# qo-100-lnb-controller.net
KiCad netlist of a schematic drawn in EAGLE
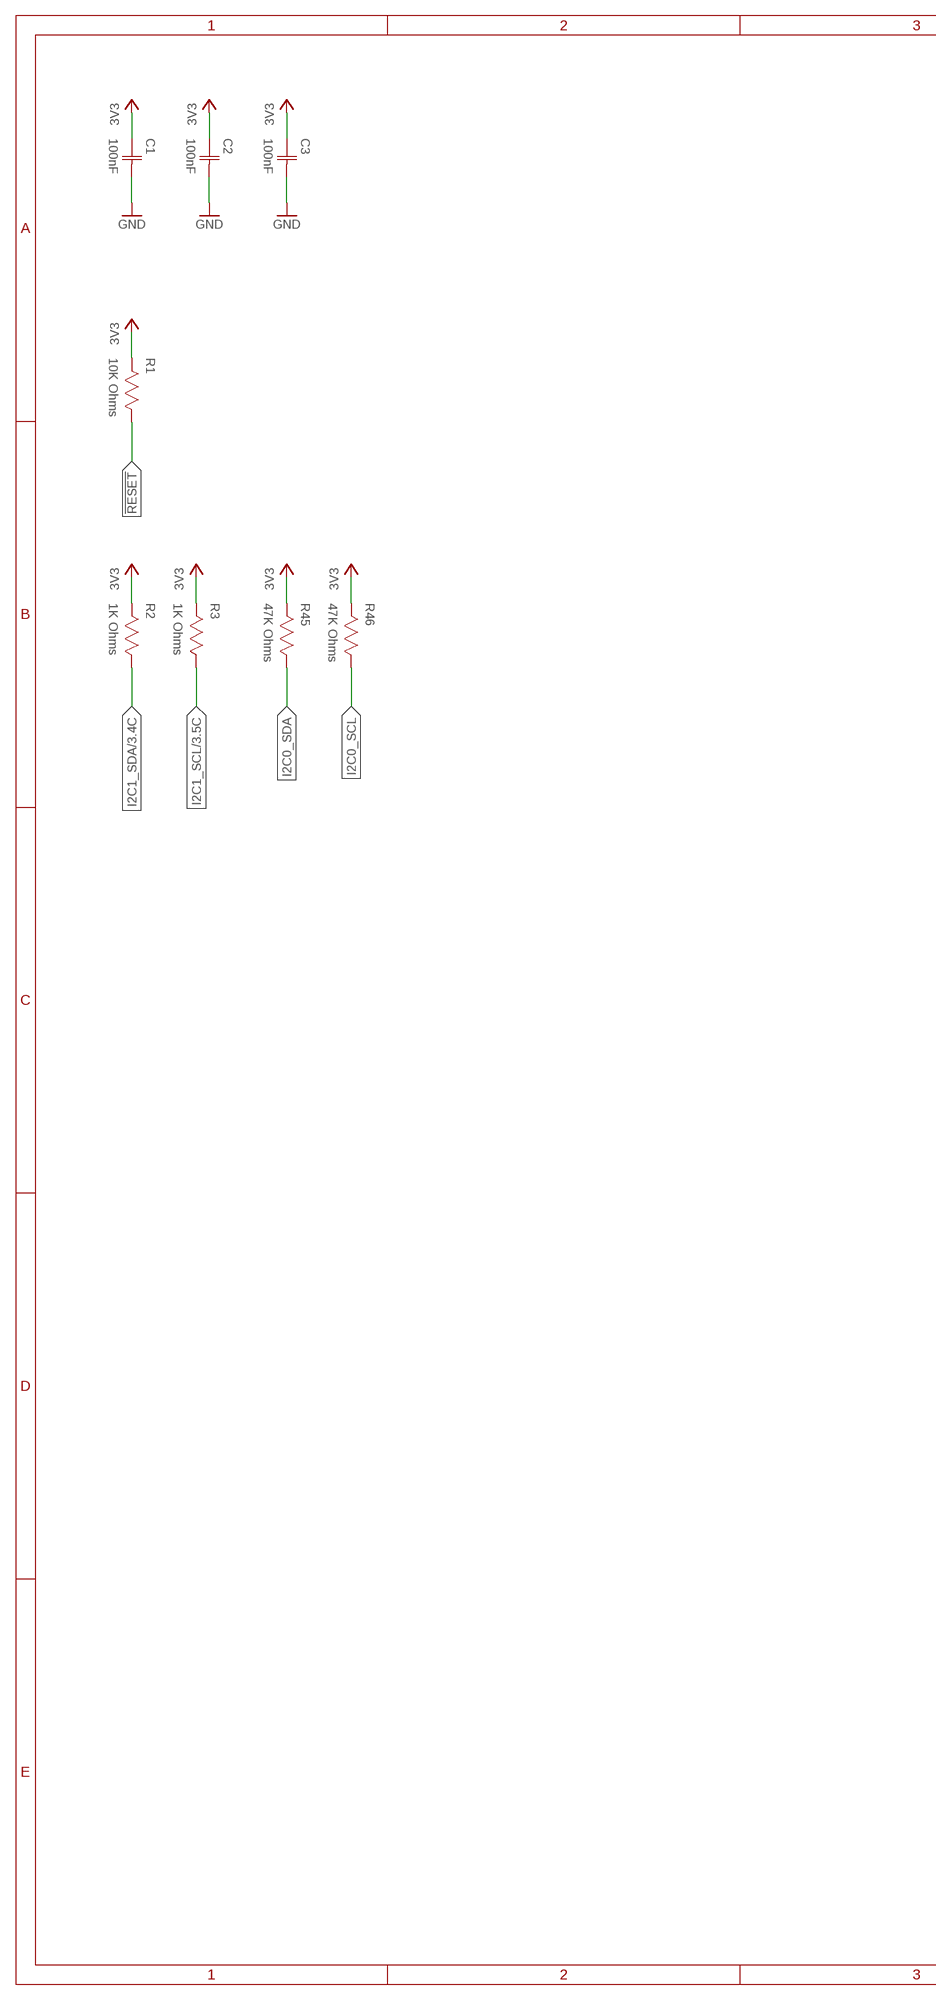
[diagram p0: schematic, sheet 1, part 1 of 2]
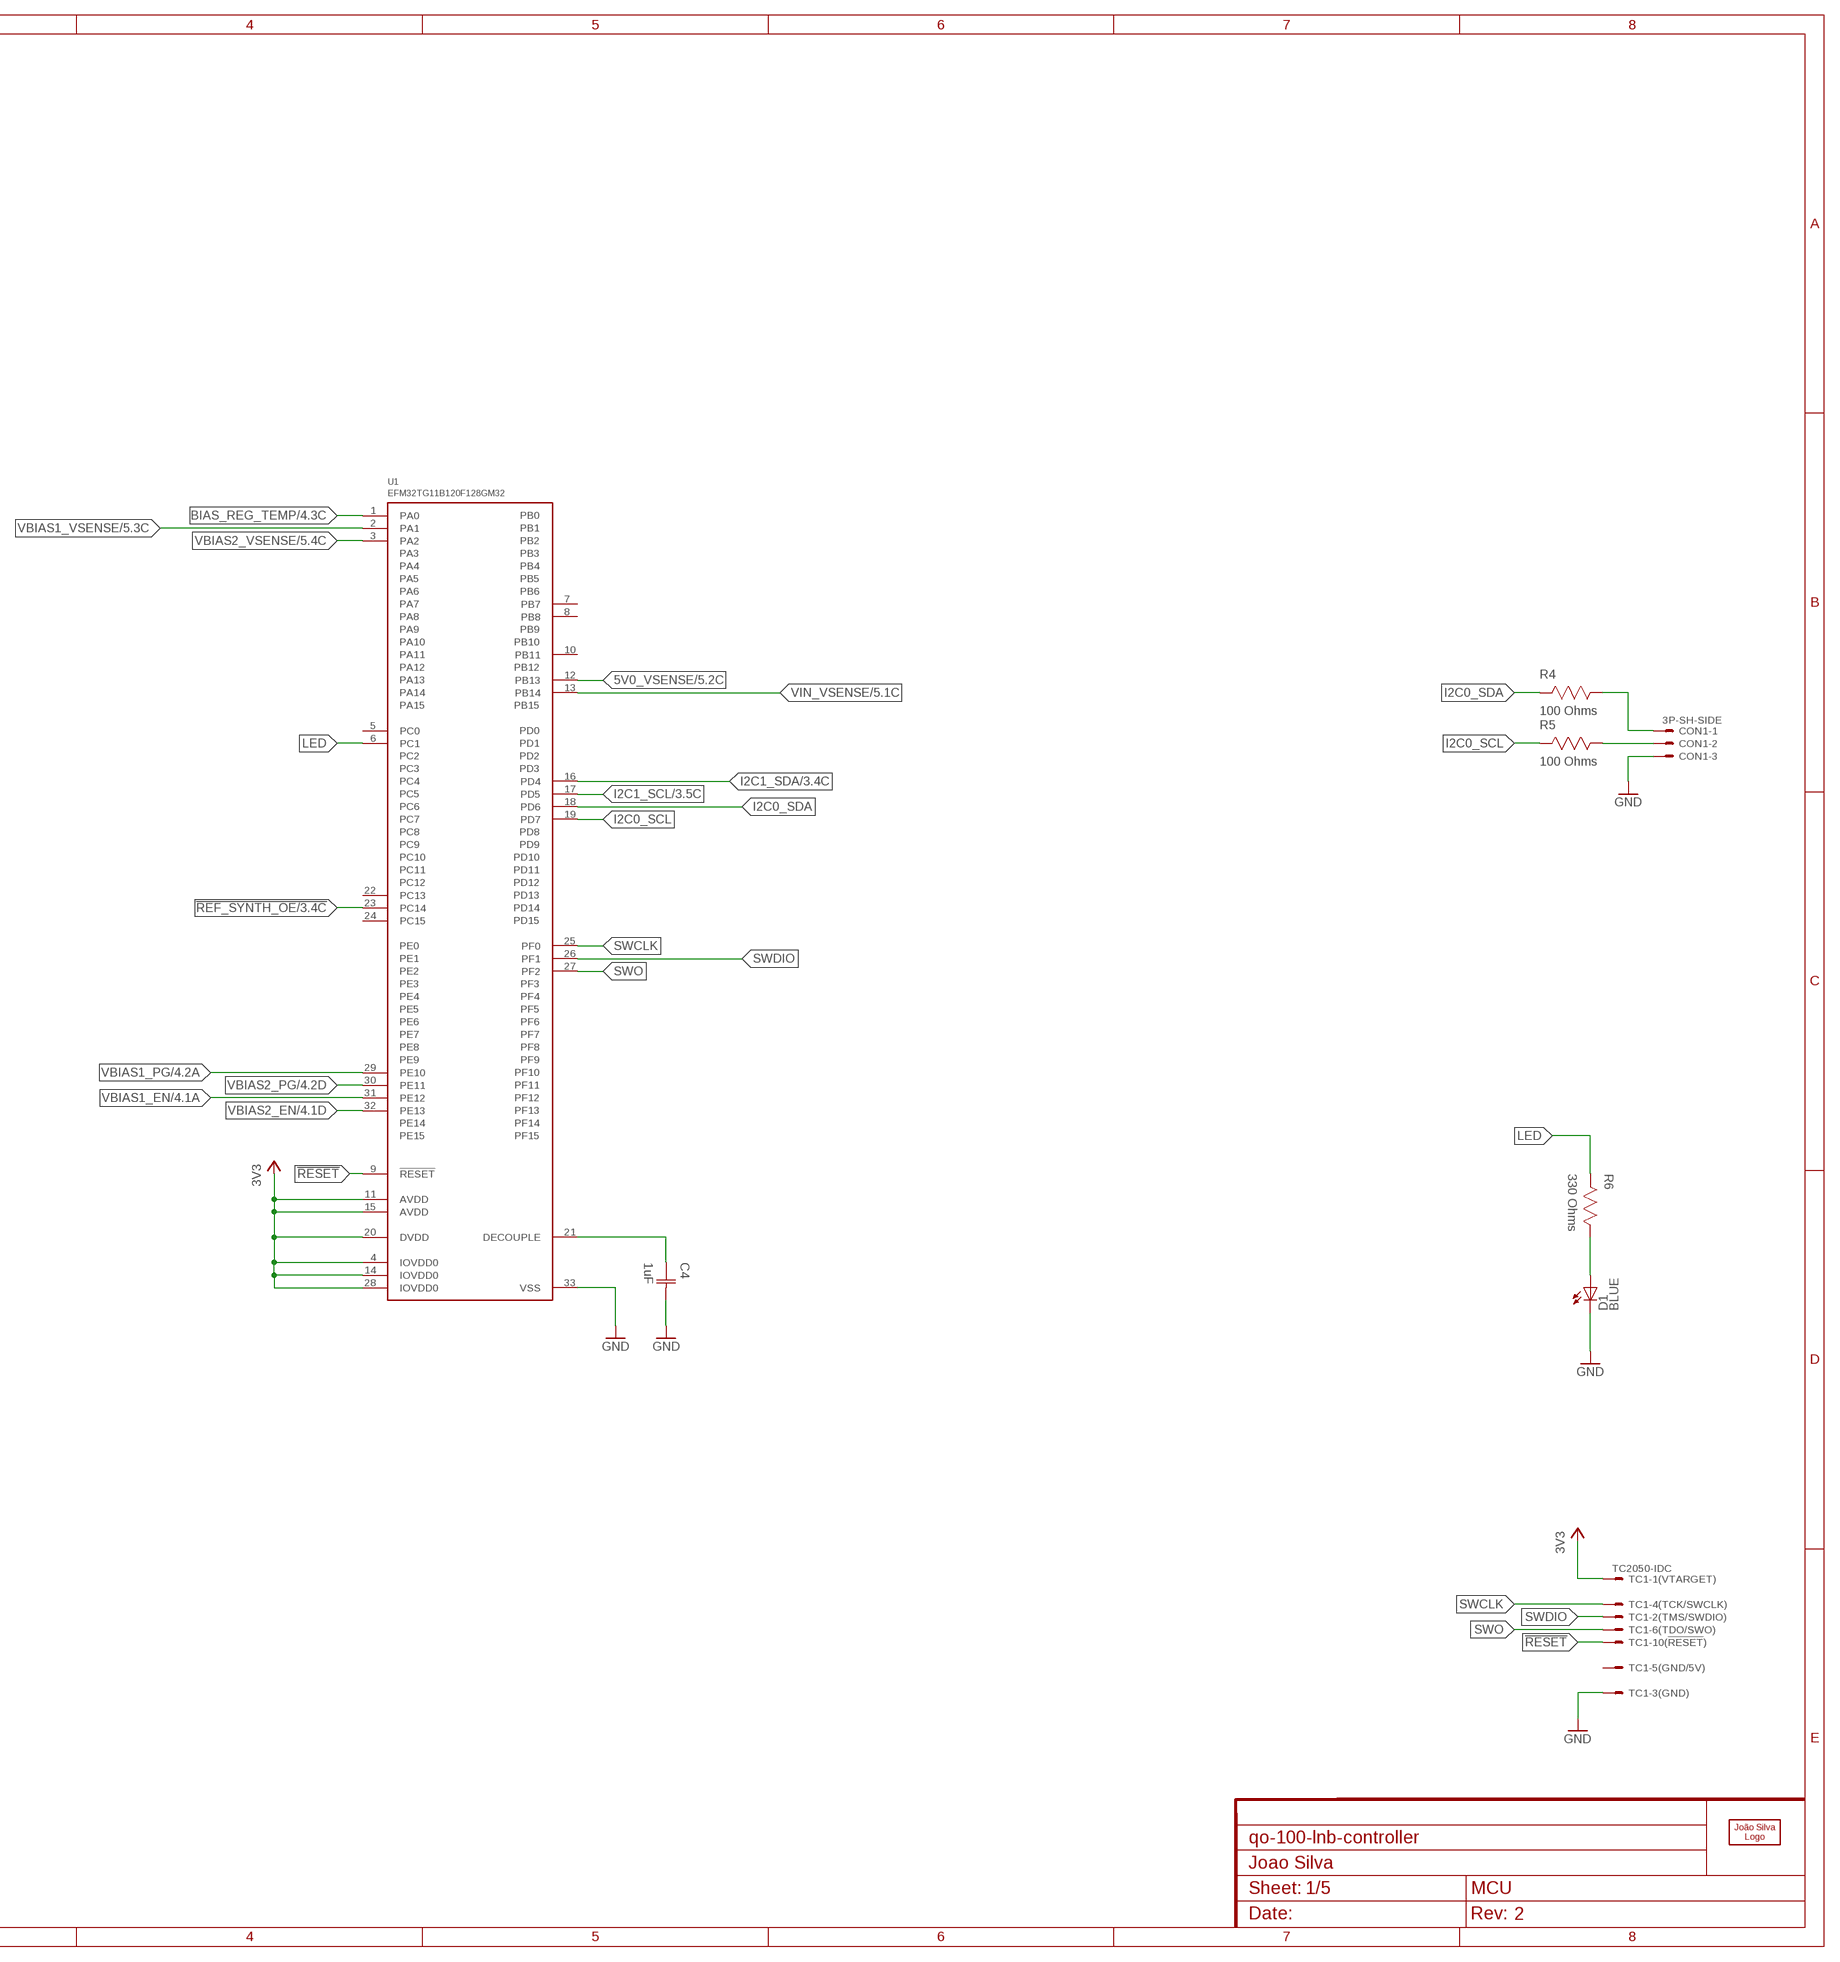
[diagram p1: schematic, sheet 1, part 2 of 2]
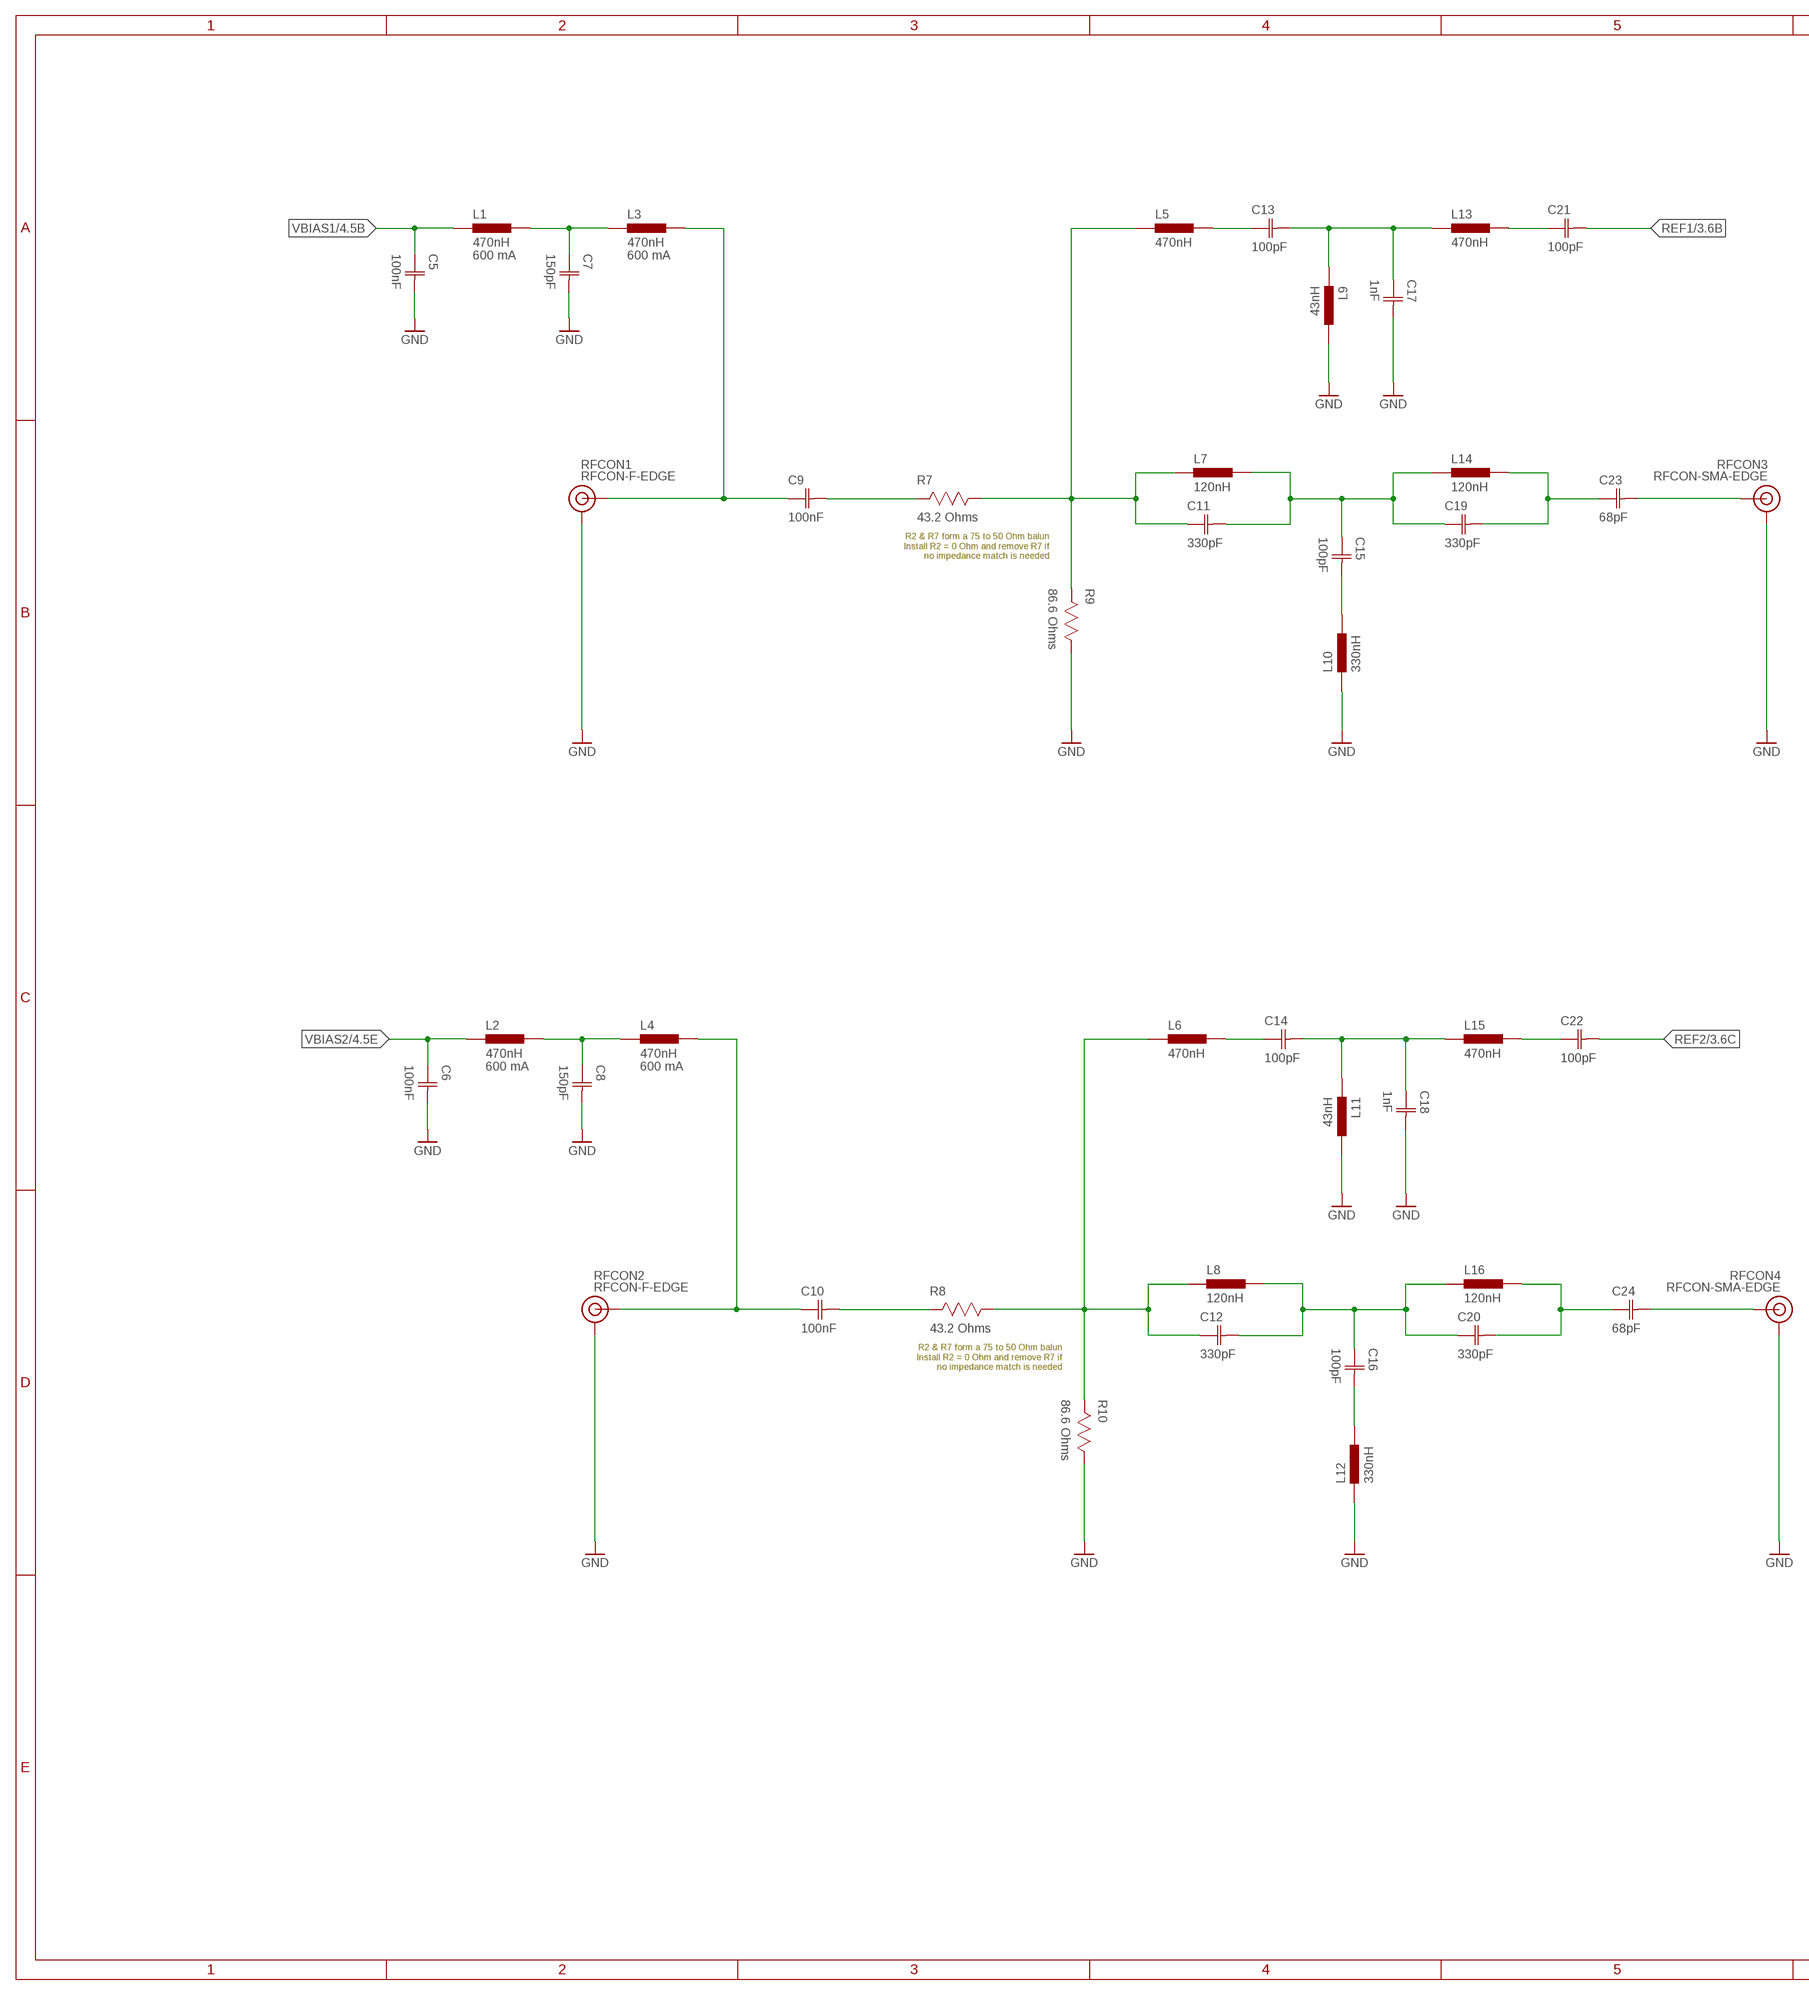
[diagram p2: schematic, sheet 2, part 1 of 2]
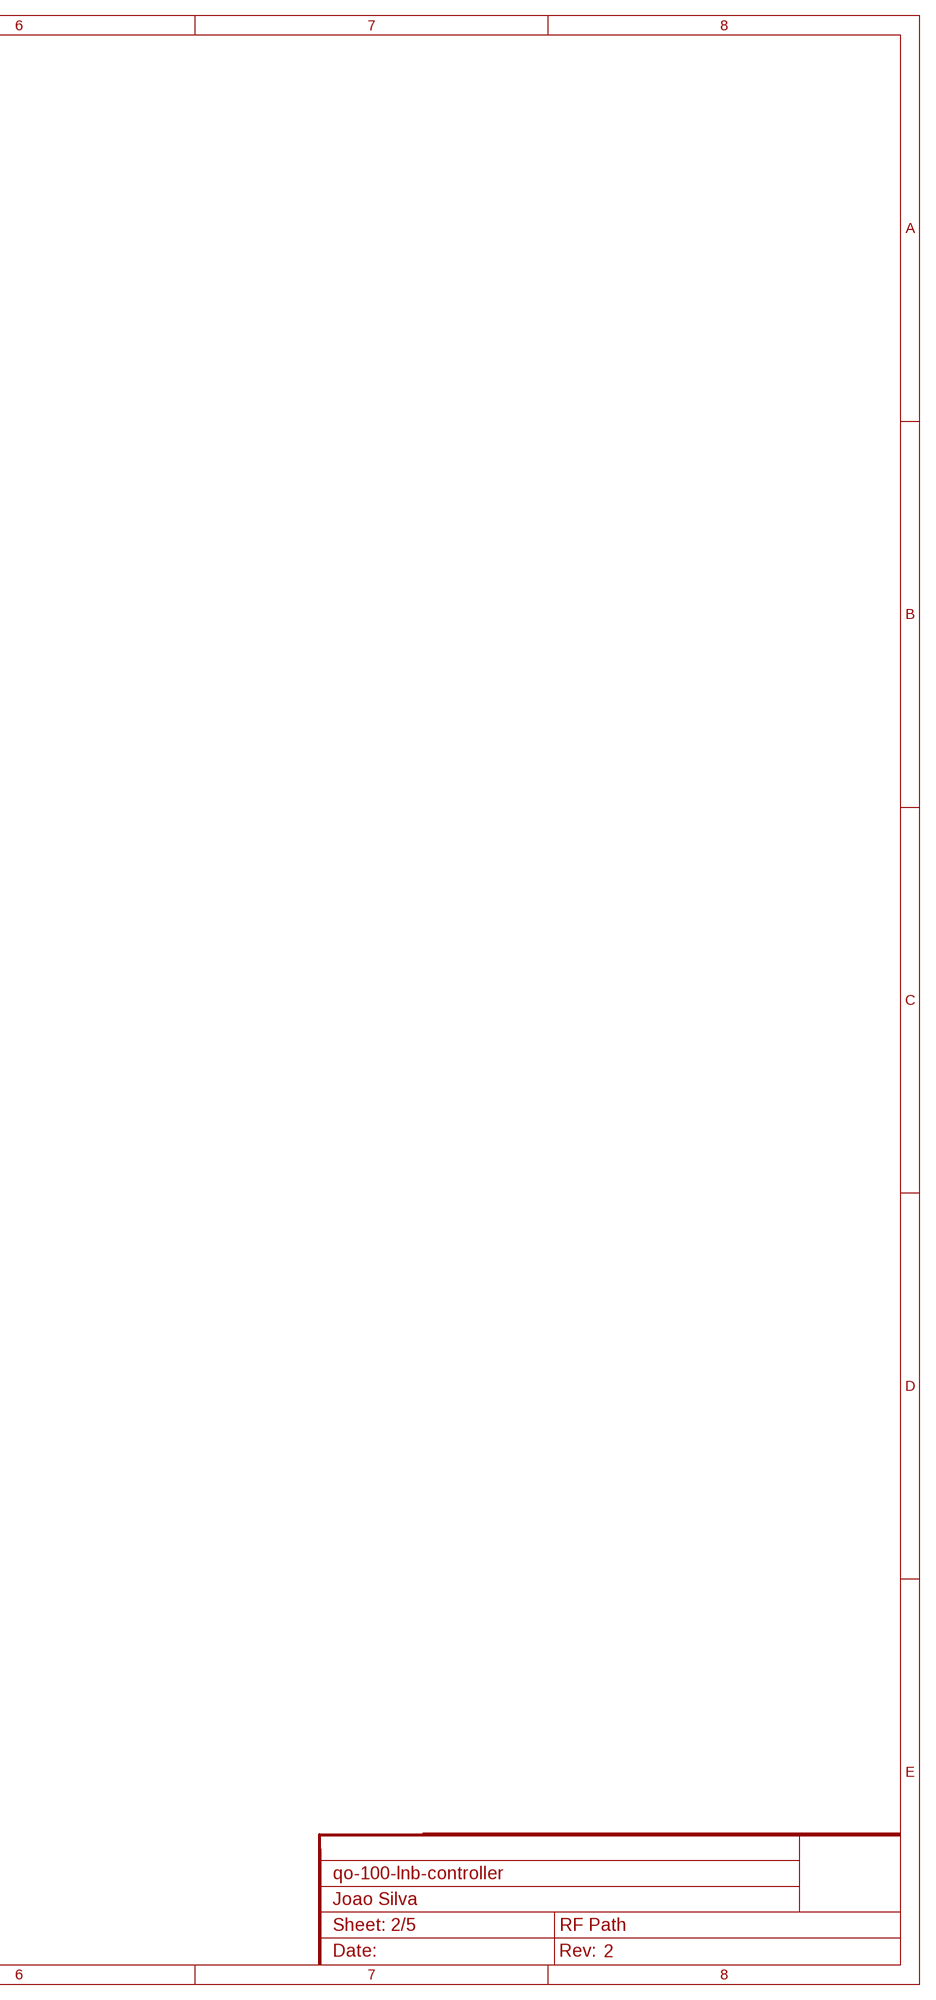
[diagram p3: schematic, sheet 2, part 2 of 2]
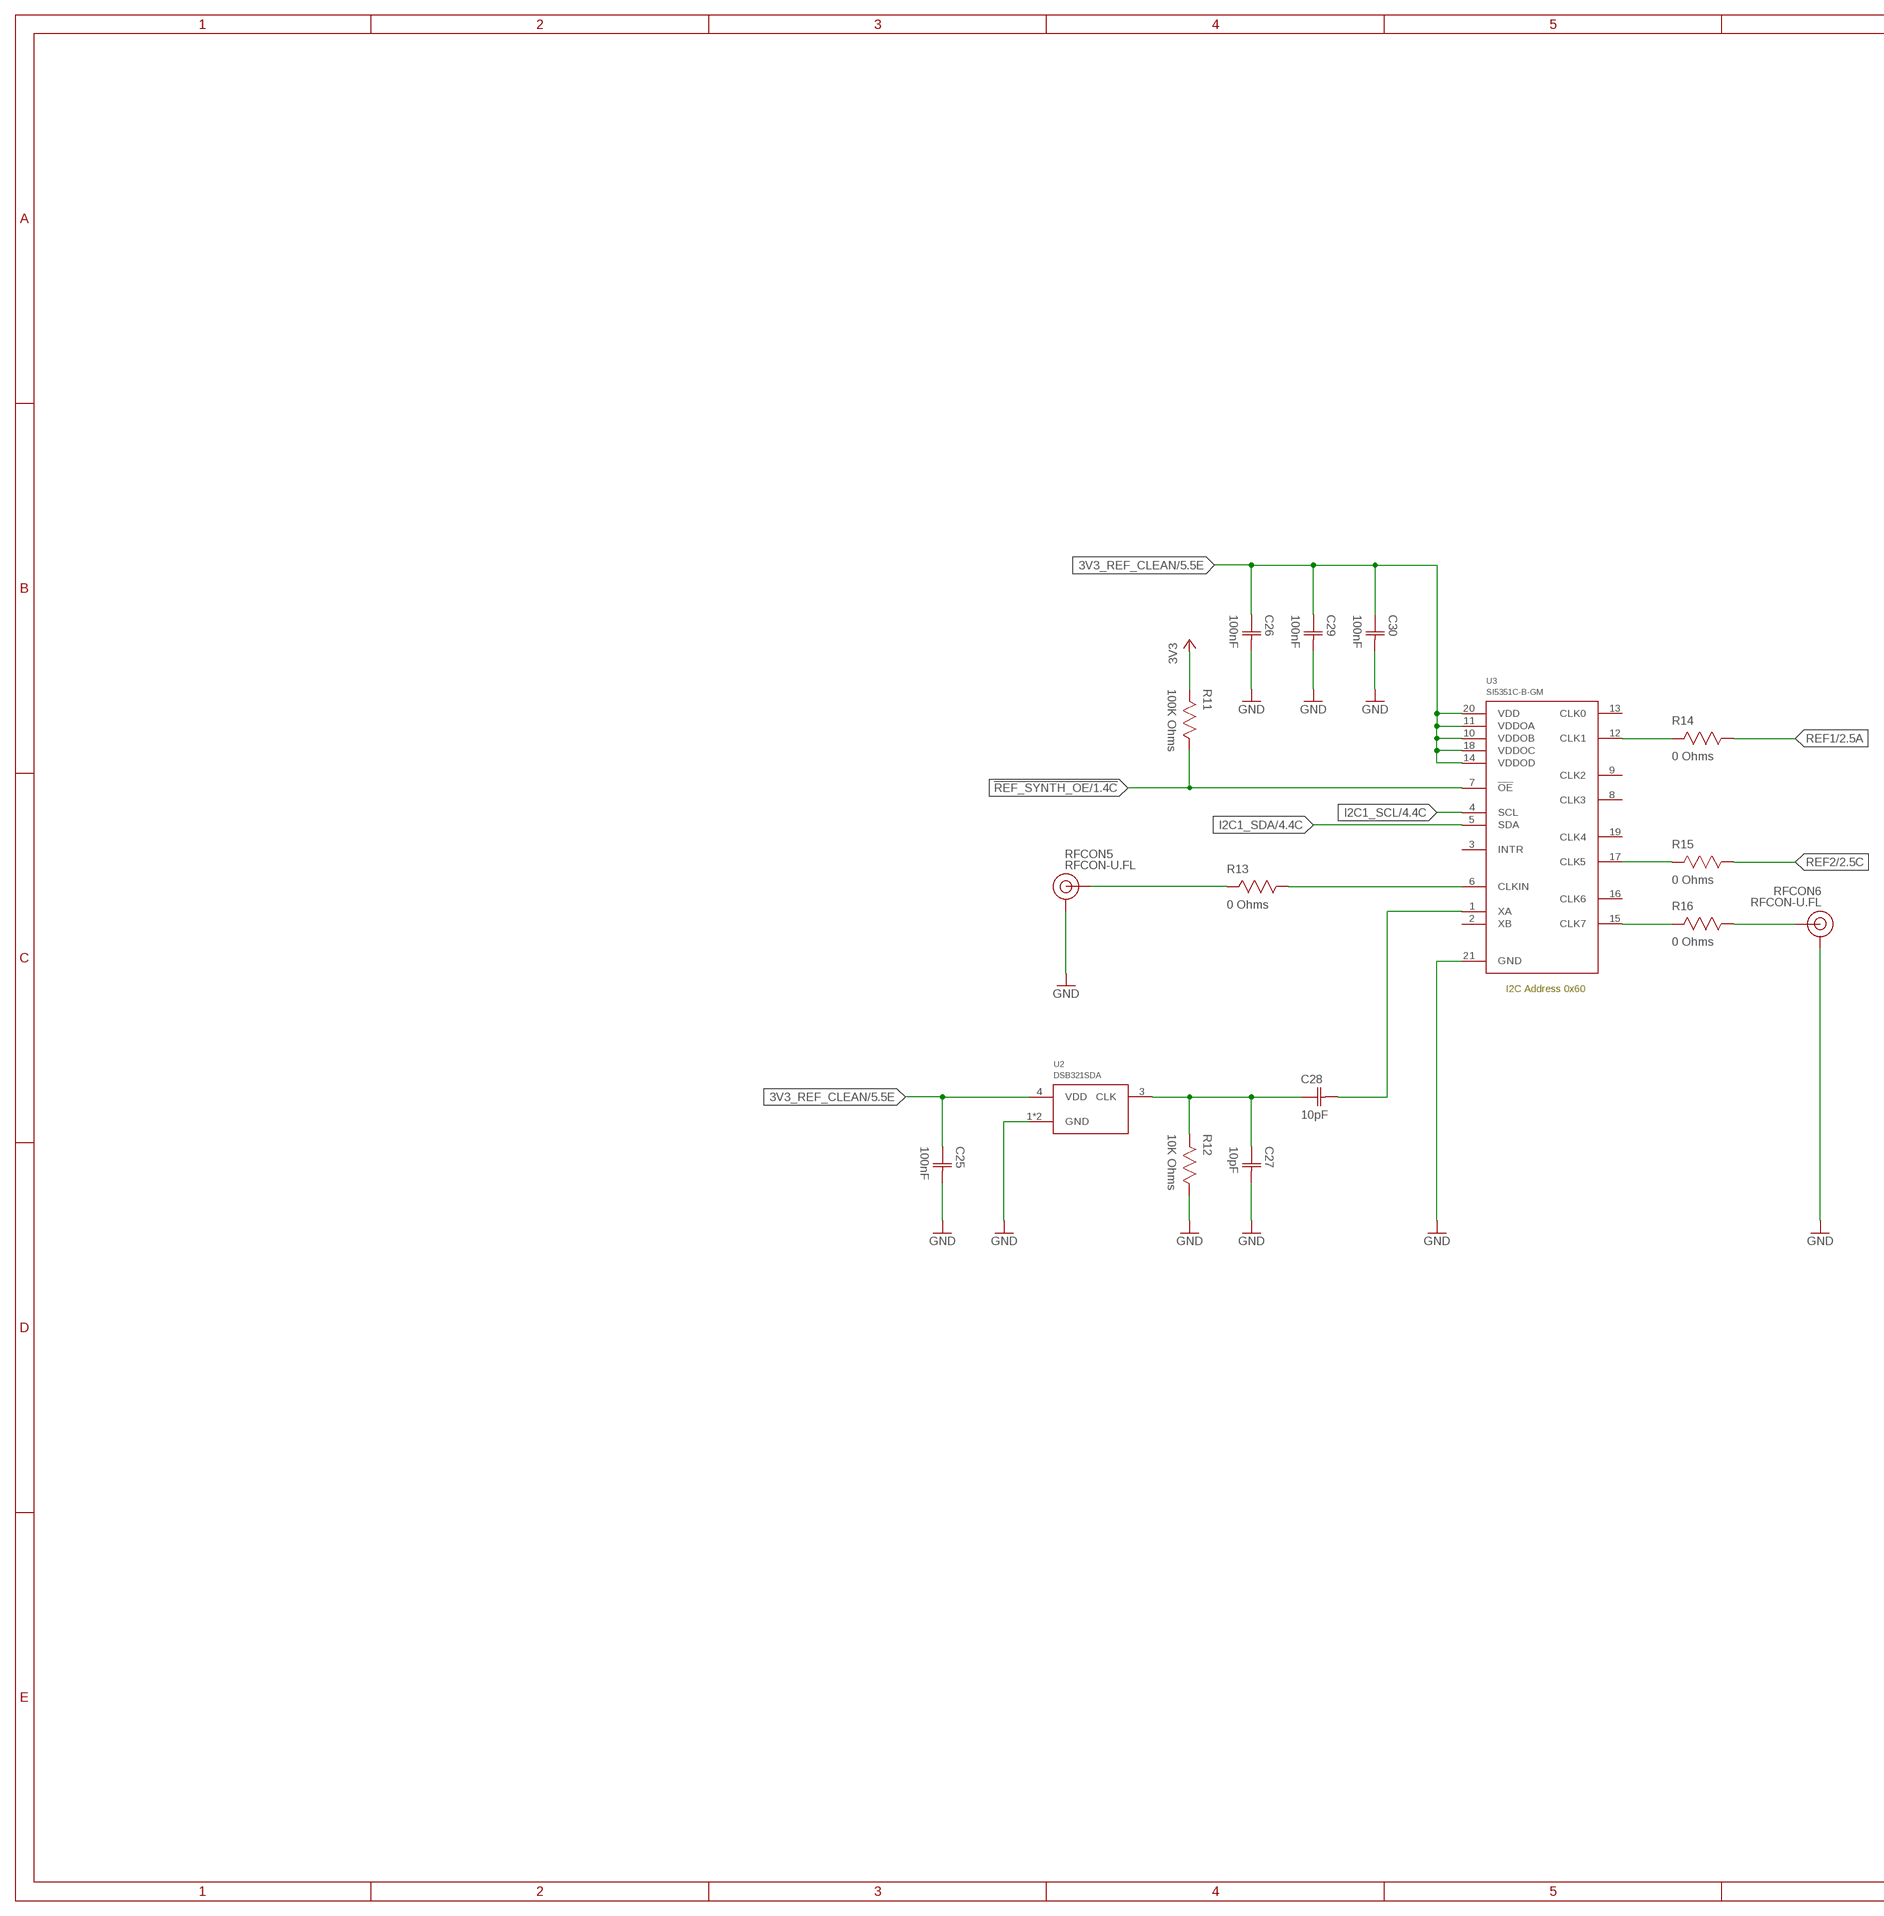
[diagram p4: schematic, sheet 3, part 1 of 2]
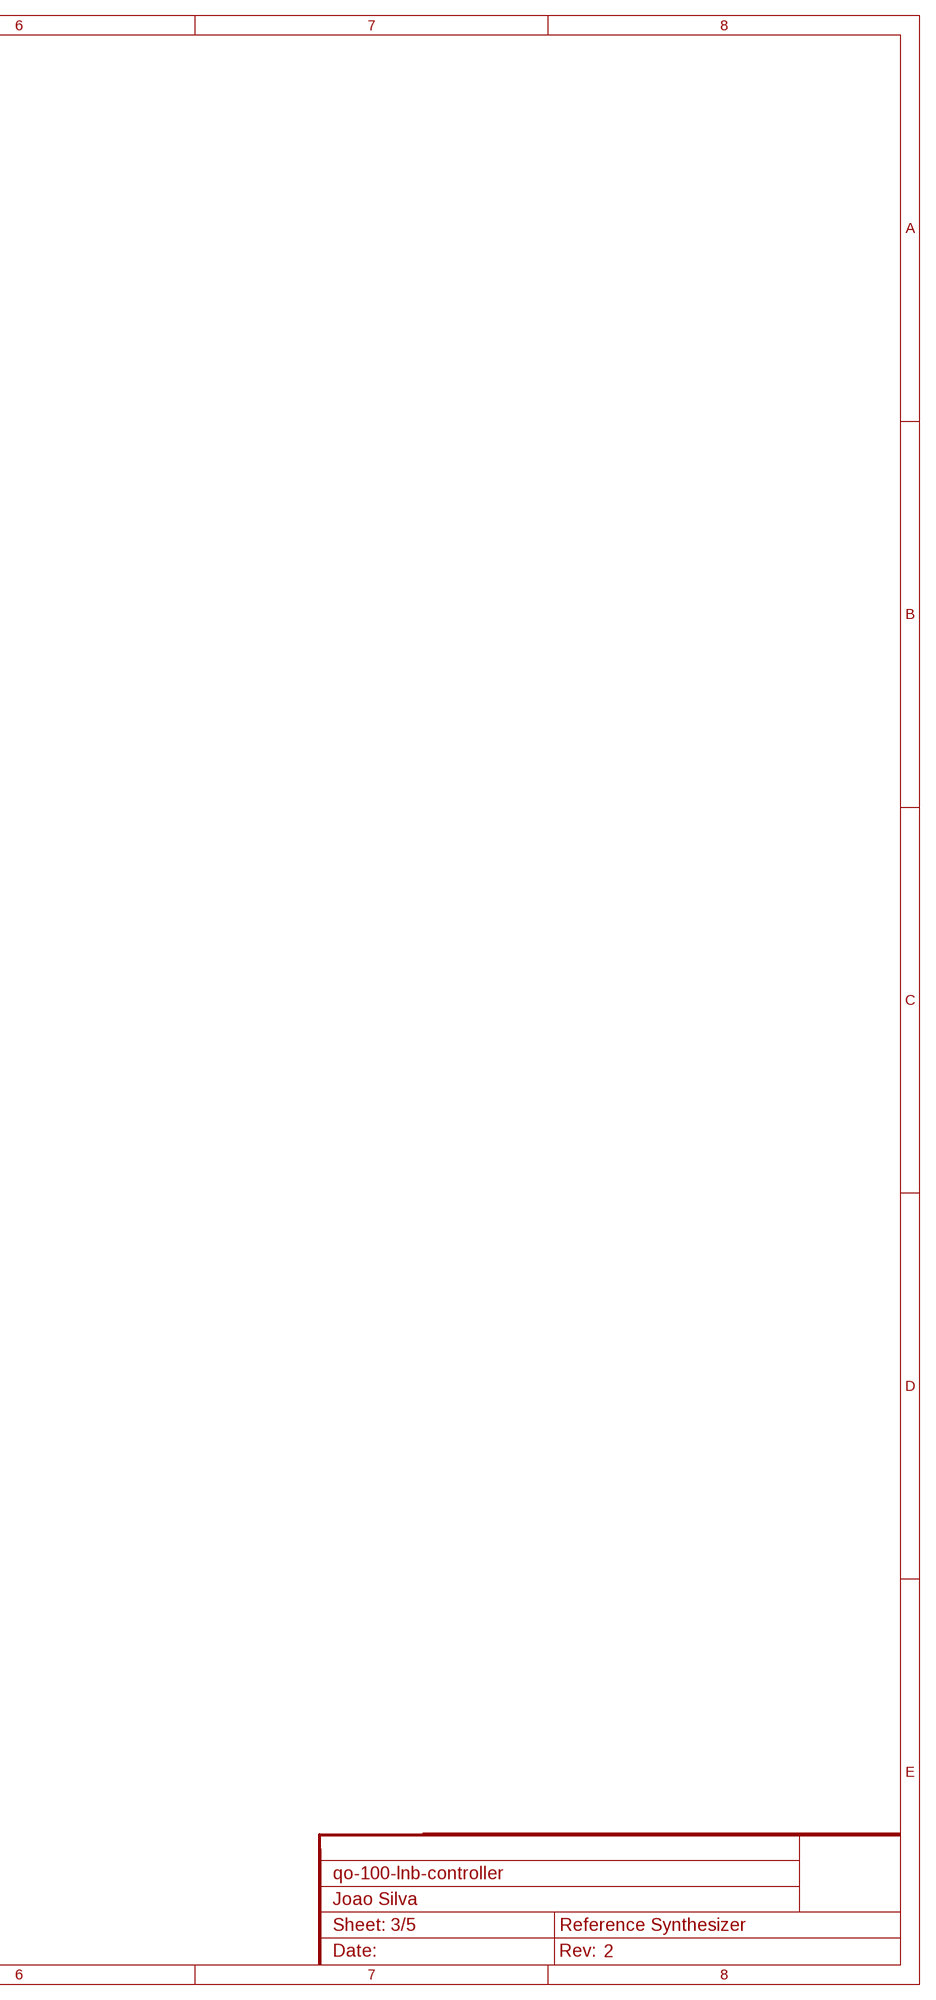
[diagram p5: schematic, sheet 3, part 2 of 2]
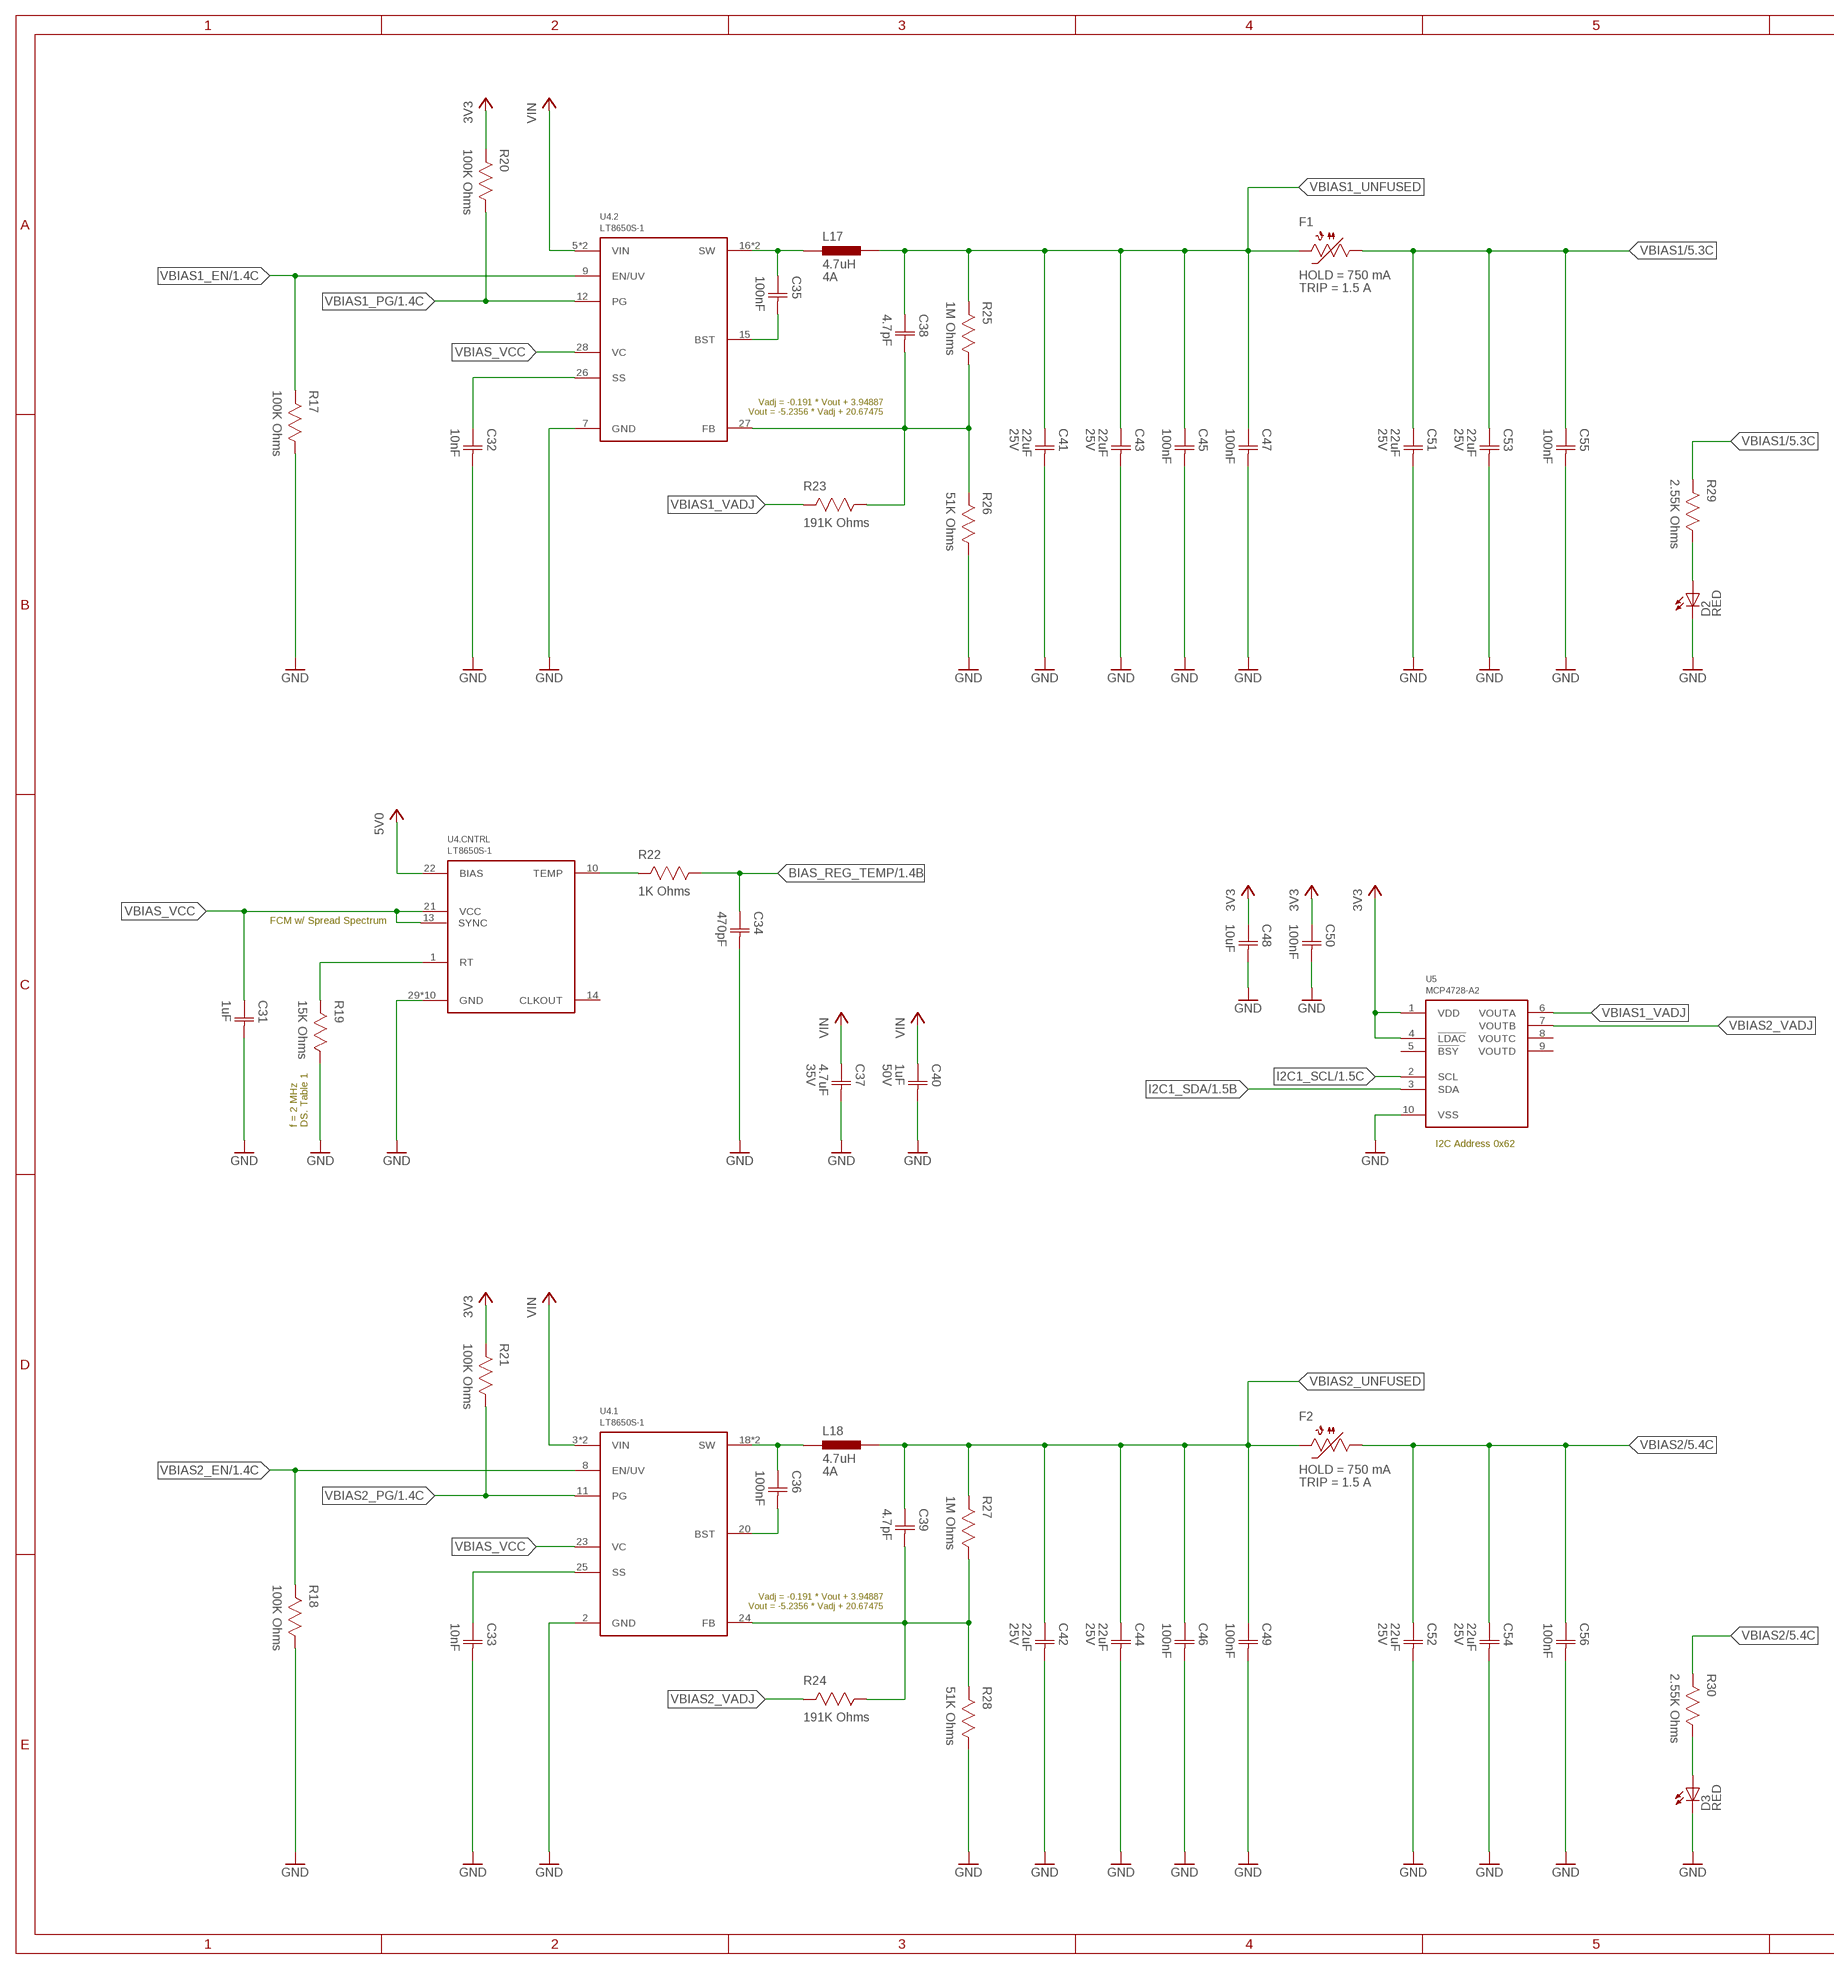
[diagram p6: schematic, sheet 4, part 1 of 2]
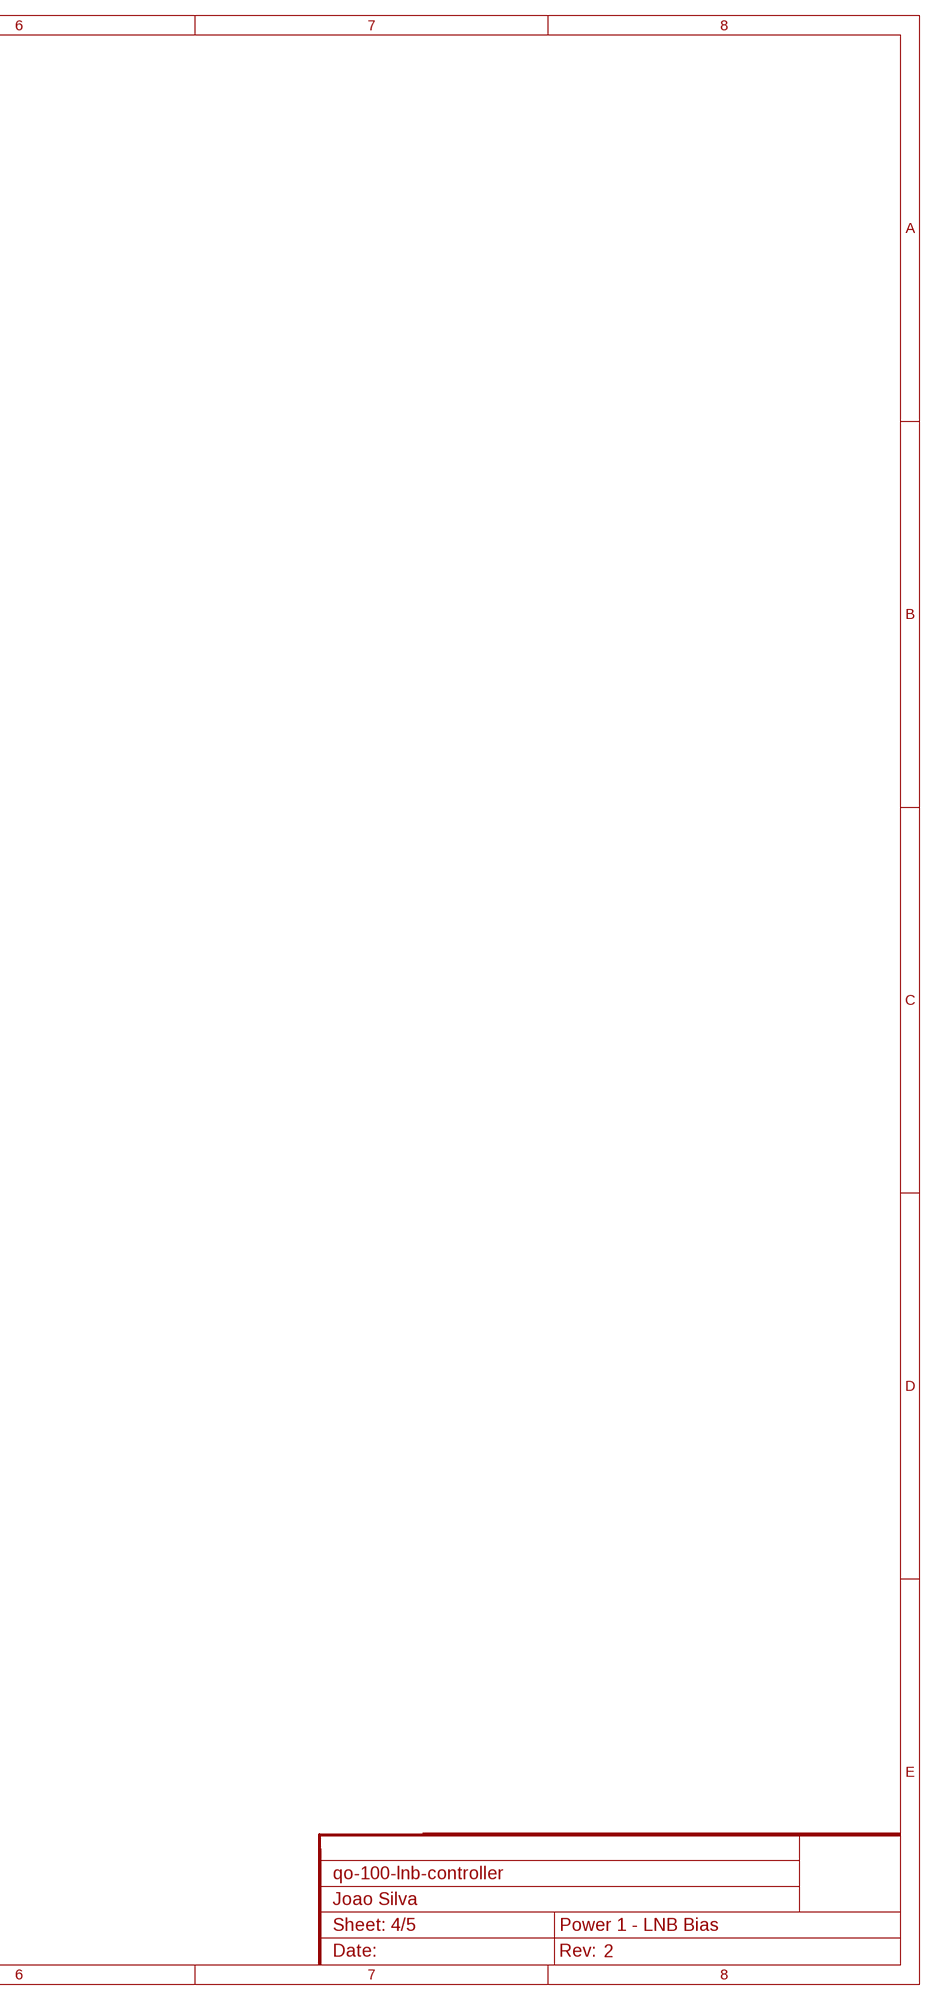
[diagram p7: schematic, sheet 4, part 2 of 2]
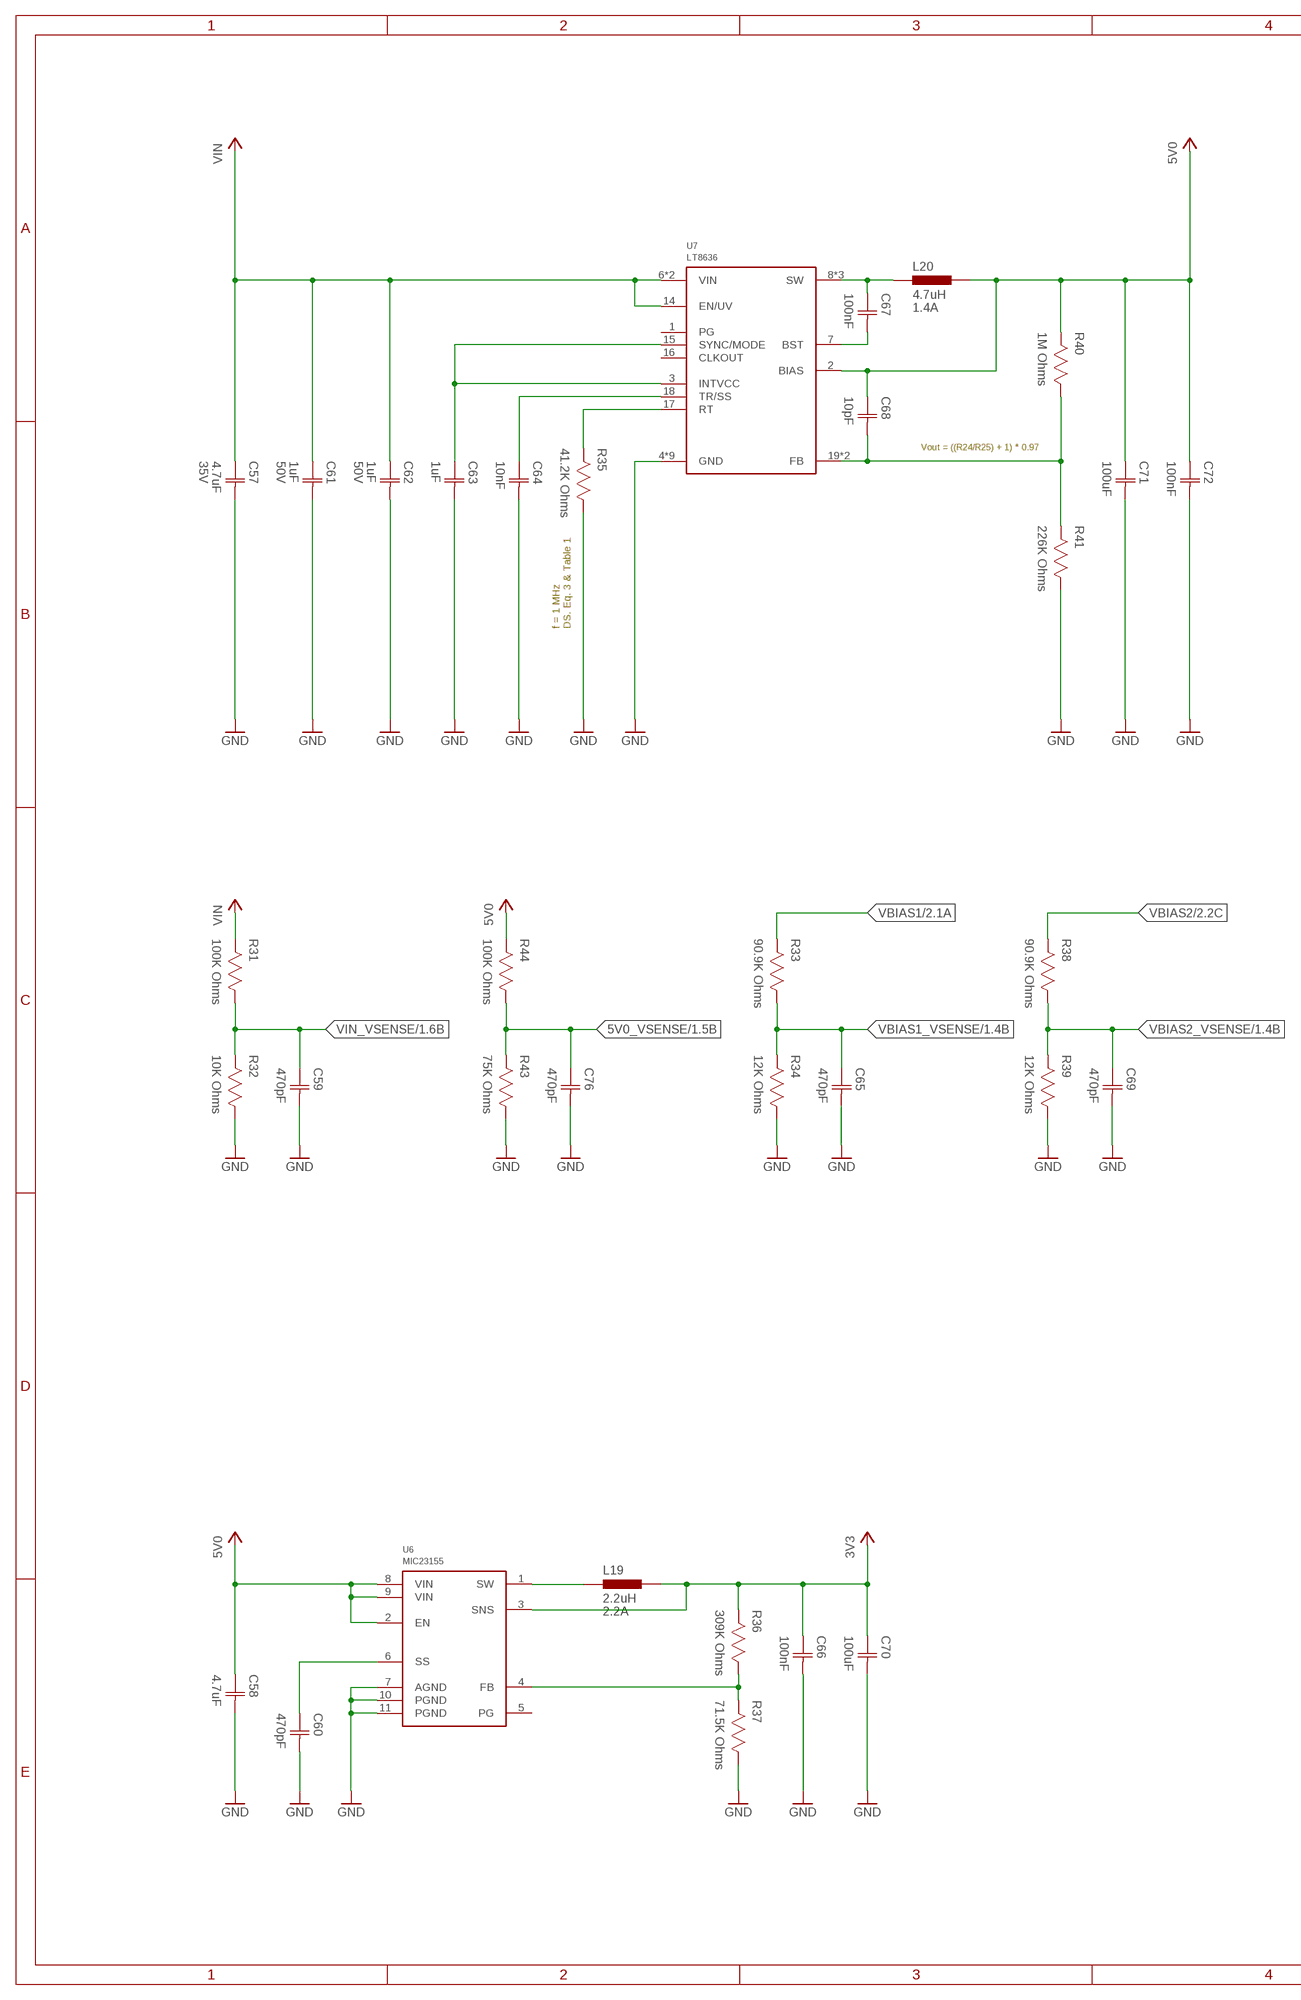
[diagram p8: schematic, sheet 5, part 1 of 2]
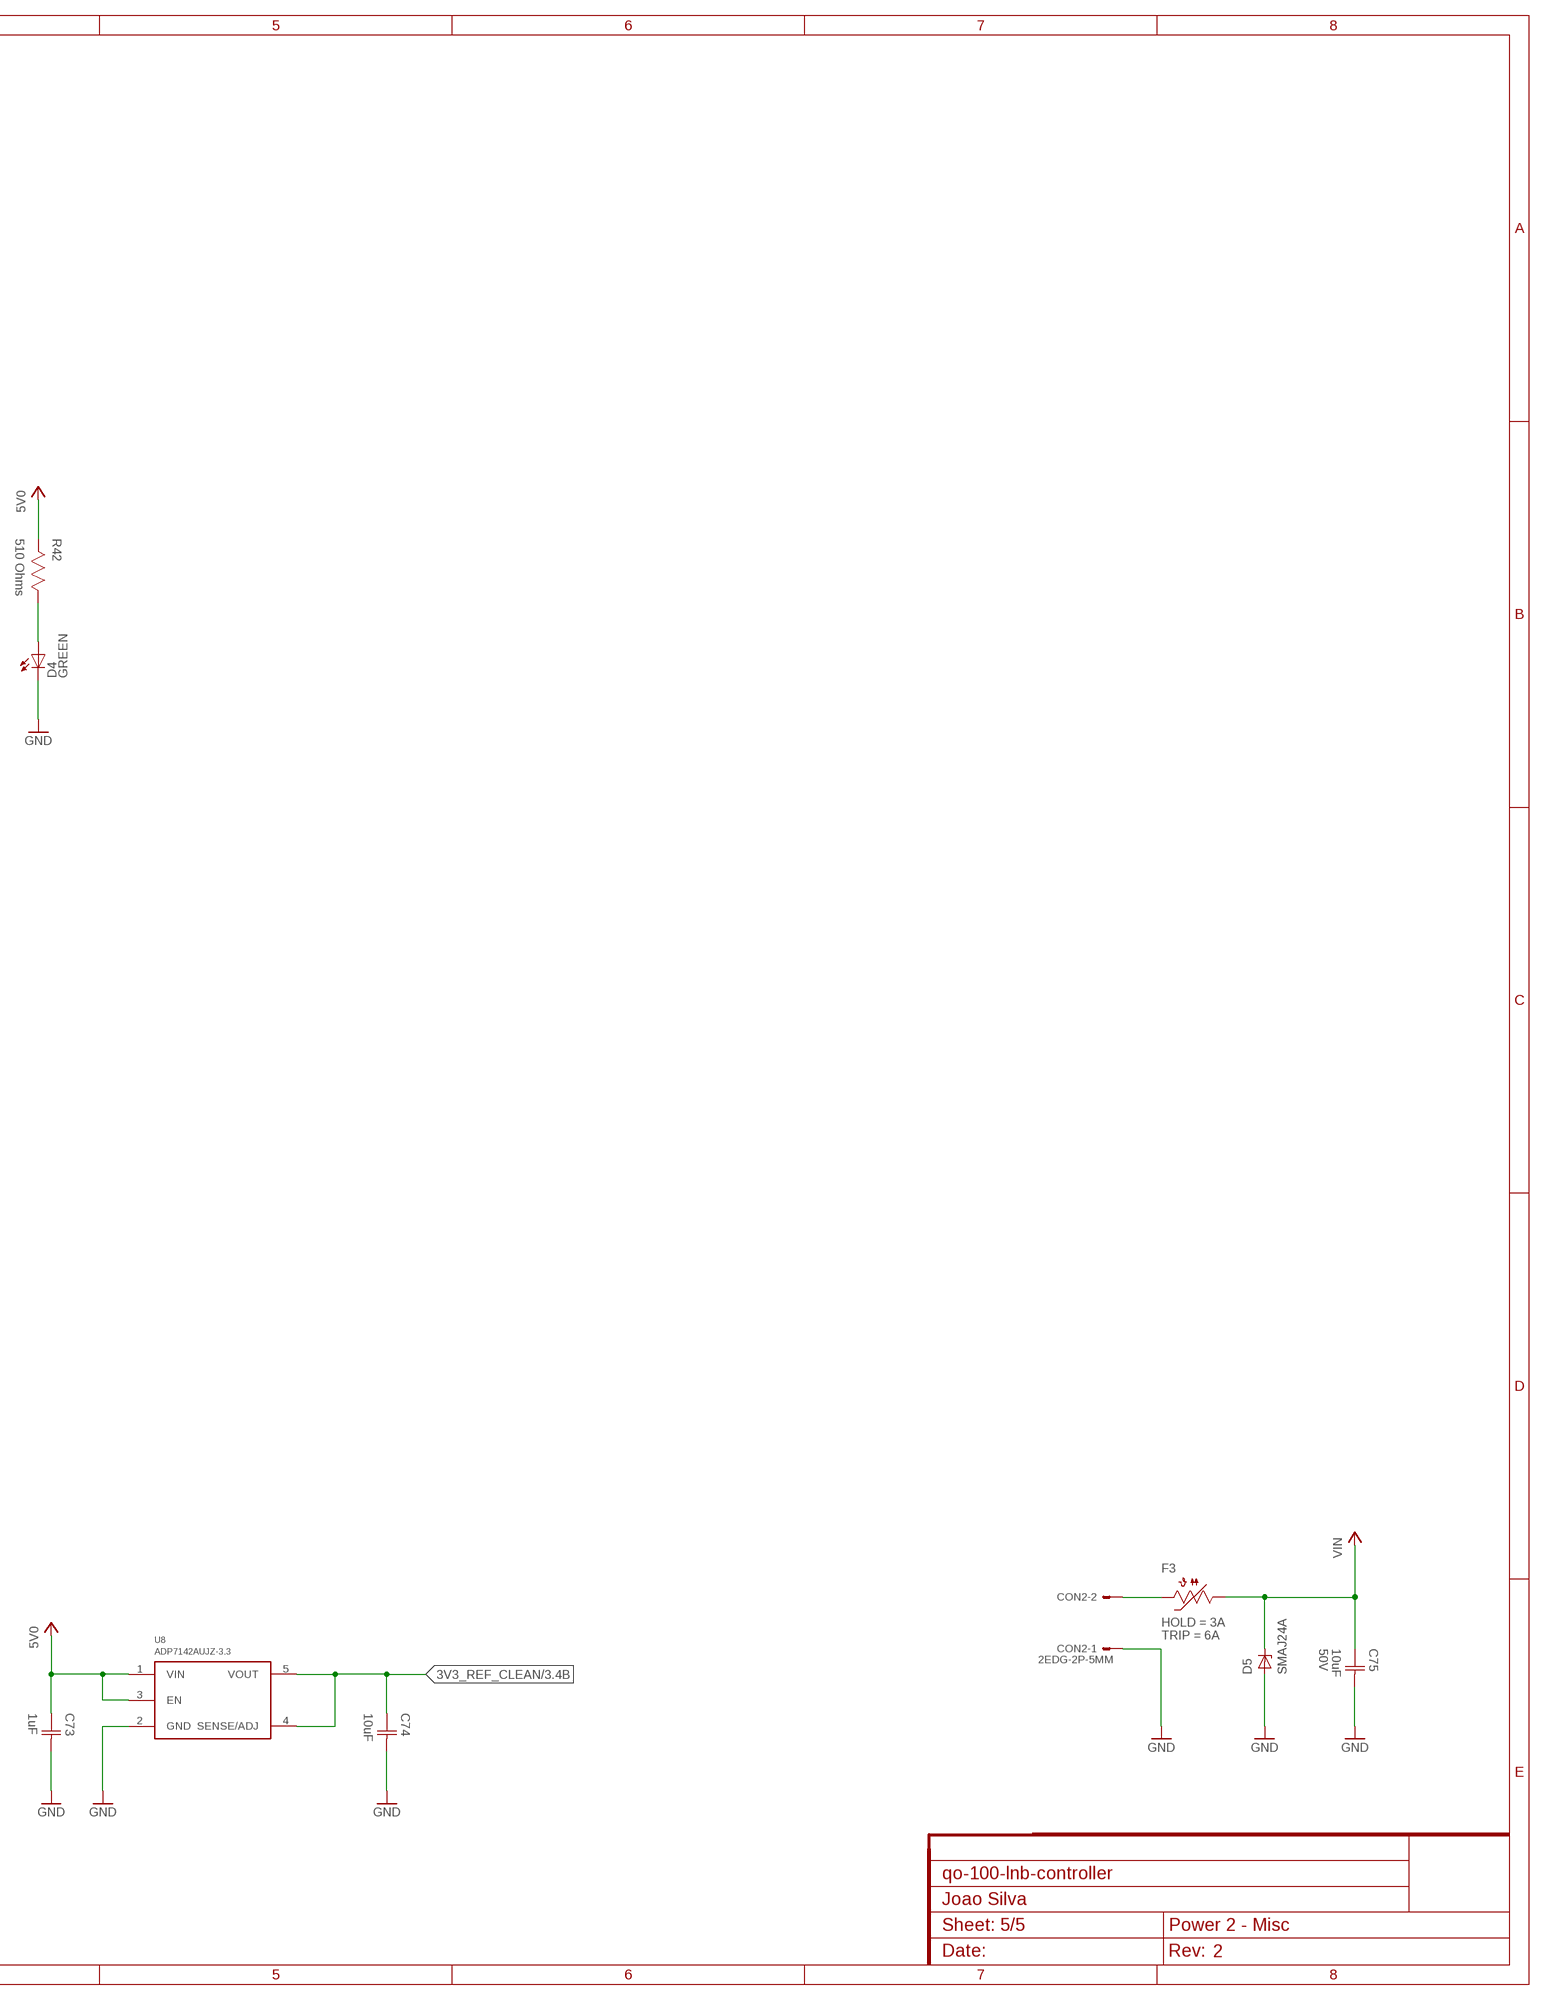
[diagram p9: schematic, sheet 5, part 2 of 2]

(export (version "E")
  (design (tool "Eeschema 10.0.6"))
  (components
    (comp (ref "C31")
      (value "1uF")
      (footprint "eagle-import:CAP0603")
      (libsource (lib "eagle-import") (part "CAPACITOR-0603"))
    )
    (comp (ref "C32")
      (value "10nF")
      (footprint "eagle-import:CAP0603")
      (libsource (lib "eagle-import") (part "CAPACITOR-0603"))
    )
    (comp (ref "C33")
      (value "10nF")
      (footprint "eagle-import:CAP0603")
      (libsource (lib "eagle-import") (part "CAPACITOR-0603"))
    )
    (comp (ref "C34")
      (value "470pF")
      (footprint "eagle-import:CAP0603")
      (libsource (lib "eagle-import") (part "CAPACITOR-0603"))
    )
    (comp (ref "C35")
      (value "100nF")
      (footprint "eagle-import:CAP0603")
      (libsource (lib "eagle-import") (part "CAPACITOR-0603"))
    )
    (comp (ref "C36")
      (value "100nF")
      (footprint "eagle-import:CAP0603")
      (libsource (lib "eagle-import") (part "CAPACITOR-0603"))
    )
    (comp (ref "C37")
      (value "4.7uF")
      (footprint "eagle-import:CAP0603")
      (fields (field (name "VOLTAGE") "35V"))
      (libsource (lib "eagle-import") (part "CAPACITOR-0603"))
    )
    (comp (ref "C38")
      (value "4.7pF")
      (footprint "eagle-import:CAP0603")
      (libsource (lib "eagle-import") (part "CAPACITOR-0603"))
    )
    (comp (ref "C39")
      (value "4.7pF")
      (footprint "eagle-import:CAP0603")
      (libsource (lib "eagle-import") (part "CAPACITOR-0603"))
    )
    (comp (ref "C40")
      (value "1uF")
      (footprint "eagle-import:CAP0603")
      (fields (field (name "VOLTAGE") "50V"))
      (libsource (lib "eagle-import") (part "CAPACITOR-0603"))
    )
    (comp (ref "C41")
      (value "22uF")
      (footprint "eagle-import:CAP1206")
      (fields (field (name "VOLTAGE") "25V"))
      (libsource (lib "eagle-import") (part "CAPACITOR-1206"))
    )
    (comp (ref "C42")
      (value "22uF")
      (footprint "eagle-import:CAP1206")
      (fields (field (name "VOLTAGE") "25V"))
      (libsource (lib "eagle-import") (part "CAPACITOR-1206"))
    )
    (comp (ref "C43")
      (value "22uF")
      (footprint "eagle-import:CAP1206")
      (fields (field (name "VOLTAGE") "25V"))
      (libsource (lib "eagle-import") (part "CAPACITOR-1206"))
    )
    (comp (ref "C44")
      (value "22uF")
      (footprint "eagle-import:CAP1206")
      (fields (field (name "VOLTAGE") "25V"))
      (libsource (lib "eagle-import") (part "CAPACITOR-1206"))
    )
    (comp (ref "C45")
      (value "100nF")
      (footprint "eagle-import:CAP0603")
      (libsource (lib "eagle-import") (part "CAPACITOR-0603"))
    )
    (comp (ref "C46")
      (value "100nF")
      (footprint "eagle-import:CAP0603")
      (libsource (lib "eagle-import") (part "CAPACITOR-0603"))
    )
    (comp (ref "C47")
      (value "100nF")
      (footprint "eagle-import:CAP0603")
      (libsource (lib "eagle-import") (part "CAPACITOR-0603"))
    )
    (comp (ref "C48")
      (value "10uF")
      (footprint "eagle-import:CAP0603")
      (libsource (lib "eagle-import") (part "CAPACITOR-0603"))
    )
    (comp (ref "C49")
      (value "100nF")
      (footprint "eagle-import:CAP0603")
      (libsource (lib "eagle-import") (part "CAPACITOR-0603"))
    )
    (comp (ref "C50")
      (value "100nF")
      (footprint "eagle-import:CAP0603")
      (libsource (lib "eagle-import") (part "CAPACITOR-0603"))
    )
    (comp (ref "C51")
      (value "22uF")
      (footprint "eagle-import:CAP1206")
      (fields (field (name "VOLTAGE") "25V"))
      (libsource (lib "eagle-import") (part "CAPACITOR-1206"))
    )
    (comp (ref "C52")
      (value "22uF")
      (footprint "eagle-import:CAP1206")
      (fields (field (name "VOLTAGE") "25V"))
      (libsource (lib "eagle-import") (part "CAPACITOR-1206"))
    )
    (comp (ref "C53")
      (value "22uF")
      (footprint "eagle-import:CAP1206")
      (fields (field (name "VOLTAGE") "25V"))
      (libsource (lib "eagle-import") (part "CAPACITOR-1206"))
    )
    (comp (ref "C54")
      (value "22uF")
      (footprint "eagle-import:CAP1206")
      (fields (field (name "VOLTAGE") "25V"))
      (libsource (lib "eagle-import") (part "CAPACITOR-1206"))
    )
    (comp (ref "C55")
      (value "100nF")
      (footprint "eagle-import:CAP0603")
      (libsource (lib "eagle-import") (part "CAPACITOR-0603"))
    )
    (comp (ref "C56")
      (value "100nF")
      (footprint "eagle-import:CAP0603")
      (libsource (lib "eagle-import") (part "CAPACITOR-0603"))
    )
    (comp (ref "D2")
      (value "LED0603")
      (footprint "eagle-import:0603")
      (fields (field (name "COLOR") "RED"))
      (libsource (lib "eagle-import") (part "LED0603"))
    )
    (comp (ref "D3")
      (value "LED0603")
      (footprint "eagle-import:0603")
      (fields (field (name "COLOR") "RED"))
      (libsource (lib "eagle-import") (part "LED0603"))
    )
    (comp (ref "F1")
      (value "PTC0805")
      (footprint "eagle-import:0805")
      (fields (field (name "HOLD") "750 mA") (field (name "TRIP") "1.5 A"))
      (libsource (lib "eagle-import") (part "PTC0805"))
    )
    (comp (ref "F2")
      (value "PTC0805")
      (footprint "eagle-import:0805")
      (fields (field (name "HOLD") "750 mA") (field (name "TRIP") "1.5 A"))
      (libsource (lib "eagle-import") (part "PTC0805"))
    )
    (comp (ref "L17")
      (value "4.7uH")
      (footprint "eagle-import:IND0404")
      (fields (field (name "CURRENT") "4A"))
      (libsource (lib "eagle-import") (part "INDUCTOR-4X4MM"))
    )
    (comp (ref "L18")
      (value "4.7uH")
      (footprint "eagle-import:IND0404")
      (fields (field (name "CURRENT") "4A"))
      (libsource (lib "eagle-import") (part "INDUCTOR-4X4MM"))
    )
    (comp (ref "R17")
      (value "100K Ohms")
      (footprint "eagle-import:RES0603")
      (libsource (lib "eagle-import") (part "RESISTOR-0603"))
    )
    (comp (ref "R18")
      (value "100K Ohms")
      (footprint "eagle-import:RES0603")
      (libsource (lib "eagle-import") (part "RESISTOR-0603"))
    )
    (comp (ref "R19")
      (value "15K Ohms")
      (footprint "eagle-import:RES0603")
      (libsource (lib "eagle-import") (part "RESISTOR-0603"))
    )
    (comp (ref "R20")
      (value "100K Ohms")
      (footprint "eagle-import:RES0603")
      (libsource (lib "eagle-import") (part "RESISTOR-0603"))
    )
    (comp (ref "R21")
      (value "100K Ohms")
      (footprint "eagle-import:RES0603")
      (libsource (lib "eagle-import") (part "RESISTOR-0603"))
    )
    (comp (ref "R22")
      (value "1K Ohms")
      (footprint "eagle-import:RES0603")
      (libsource (lib "eagle-import") (part "RESISTOR-0603"))
    )
    (comp (ref "R23")
      (value "191K Ohms")
      (footprint "eagle-import:RES0603")
      (libsource (lib "eagle-import") (part "RESISTOR-0603"))
    )
    (comp (ref "R24")
      (value "191K Ohms")
      (footprint "eagle-import:RES0603")
      (libsource (lib "eagle-import") (part "RESISTOR-0603"))
    )
    (comp (ref "R25")
      (value "1M Ohms")
      (footprint "eagle-import:RES0603")
      (libsource (lib "eagle-import") (part "RESISTOR-0603"))
    )
    (comp (ref "R26")
      (value "51K Ohms")
      (footprint "eagle-import:RES0603")
      (libsource (lib "eagle-import") (part "RESISTOR-0603"))
    )
    (comp (ref "R27")
      (value "1M Ohms")
      (footprint "eagle-import:RES0603")
      (libsource (lib "eagle-import") (part "RESISTOR-0603"))
    )
    (comp (ref "R28")
      (value "51K Ohms")
      (footprint "eagle-import:RES0603")
      (libsource (lib "eagle-import") (part "RESISTOR-0603"))
    )
    (comp (ref "R29")
      (value "2.55K Ohms")
      (footprint "eagle-import:RES0603")
      (libsource (lib "eagle-import") (part "RESISTOR-0603"))
    )
    (comp (ref "R30")
      (value "2.55K Ohms")
      (footprint "eagle-import:RES0603")
      (libsource (lib "eagle-import") (part "RESISTOR-0603"))
    )
    (comp (ref "U4")
      (value "LT8650S-1")
      (footprint "eagle-import:QFN28_ASYM_CORNER")
      (libsource (lib "eagle-import") (part "LT8650S-1"))
    )
    (comp (ref "U5")
      (value "MCP4728-A2")
      (footprint "eagle-import:MSOP10")
      (libsource (lib "eagle-import") (part "MCP4728-A2"))
    )
    (comp (ref "C1")
      (value "100nF")
      (footprint "eagle-import:CAP0603")
      (libsource (lib "eagle-import") (part "CAPACITOR-0603"))
    )
    (comp (ref "C2")
      (value "100nF")
      (footprint "eagle-import:CAP0603")
      (libsource (lib "eagle-import") (part "CAPACITOR-0603"))
    )
    (comp (ref "C3")
      (value "100nF")
      (footprint "eagle-import:CAP0603")
      (libsource (lib "eagle-import") (part "CAPACITOR-0603"))
    )
    (comp (ref "C4")
      (value "1uF")
      (footprint "eagle-import:CAP0603")
      (libsource (lib "eagle-import") (part "CAPACITOR-0603"))
    )
    (comp (ref "CON1")
      (value "3P-SH-SIDE")
      (footprint "eagle-import:SH-03-SIDE")
      (libsource (lib "eagle-import") (part "3P-SH-SIDE"))
    )
    (comp (ref "D1")
      (value "LED0603")
      (footprint "eagle-import:0603")
      (fields (field (name "COLOR") "BLUE"))
      (libsource (lib "eagle-import") (part "LED0603"))
    )
    (comp (ref "LOGO1")
      (value "JS-10MM")
      (footprint "eagle-import:JS_10MM")
      (libsource (lib "eagle-import") (part "JS-10MM"))
    )
    (comp (ref "R1")
      (value "10K Ohms")
      (footprint "eagle-import:RES0603")
      (libsource (lib "eagle-import") (part "RESISTOR-0603"))
    )
    (comp (ref "R2")
      (value "1K Ohms")
      (footprint "eagle-import:RES0603")
      (libsource (lib "eagle-import") (part "RESISTOR-0603"))
    )
    (comp (ref "R3")
      (value "1K Ohms")
      (footprint "eagle-import:RES0603")
      (libsource (lib "eagle-import") (part "RESISTOR-0603"))
    )
    (comp (ref "R4")
      (value "100 Ohms")
      (footprint "eagle-import:RES0603")
      (libsource (lib "eagle-import") (part "RESISTOR-0603"))
    )
    (comp (ref "R5")
      (value "100 Ohms")
      (footprint "eagle-import:RES0603")
      (libsource (lib "eagle-import") (part "RESISTOR-0603"))
    )
    (comp (ref "R6")
      (value "330 Ohms")
      (footprint "eagle-import:RES0603")
      (libsource (lib "eagle-import") (part "RESISTOR-0603"))
    )
    (comp (ref "R45")
      (value "47K Ohms")
      (footprint "eagle-import:RES0603")
      (libsource (lib "eagle-import") (part "RESISTOR-0603"))
    )
    (comp (ref "R46")
      (value "47K Ohms")
      (footprint "eagle-import:RES0603")
      (libsource (lib "eagle-import") (part "RESISTOR-0603"))
    )
    (comp (ref "TC1")
      (value "TC2050-IDC")
      (footprint "eagle-import:TC2050-IDC")
      (libsource (lib "eagle-import") (part "TC2050-IDC"))
    )
    (comp (ref "U1")
      (value "EFM32TG11B120F128GM32")
      (footprint "eagle-import:QFN32_0.5P_TG")
      (libsource (lib "eagle-import") (part "EFM32TG11B1M3220F128G"))
    )
    (comp (ref "C57")
      (value "4.7uF")
      (footprint "eagle-import:CAP0603")
      (fields (field (name "VOLTAGE") "35V"))
      (libsource (lib "eagle-import") (part "CAPACITOR-0603"))
    )
    (comp (ref "C58")
      (value "4.7uF")
      (footprint "eagle-import:CAP0603")
      (libsource (lib "eagle-import") (part "CAPACITOR-0603"))
    )
    (comp (ref "C59")
      (value "470pF")
      (footprint "eagle-import:CAP0603")
      (libsource (lib "eagle-import") (part "CAPACITOR-0603"))
    )
    (comp (ref "C60")
      (value "470pF")
      (footprint "eagle-import:CAP0603")
      (libsource (lib "eagle-import") (part "CAPACITOR-0603"))
    )
    (comp (ref "C61")
      (value "1uF")
      (footprint "eagle-import:CAP0603")
      (fields (field (name "VOLTAGE") "50V"))
      (libsource (lib "eagle-import") (part "CAPACITOR-0603"))
    )
    (comp (ref "C62")
      (value "1uF")
      (footprint "eagle-import:CAP0603")
      (fields (field (name "VOLTAGE") "50V"))
      (libsource (lib "eagle-import") (part "CAPACITOR-0603"))
    )
    (comp (ref "C63")
      (value "1uF")
      (footprint "eagle-import:CAP0603")
      (libsource (lib "eagle-import") (part "CAPACITOR-0603"))
    )
    (comp (ref "C64")
      (value "10nF")
      (footprint "eagle-import:CAP0603")
      (libsource (lib "eagle-import") (part "CAPACITOR-0603"))
    )
    (comp (ref "C65")
      (value "470pF")
      (footprint "eagle-import:CAP0603")
      (libsource (lib "eagle-import") (part "CAPACITOR-0603"))
    )
    (comp (ref "C66")
      (value "100nF")
      (footprint "eagle-import:CAP0603")
      (libsource (lib "eagle-import") (part "CAPACITOR-0603"))
    )
    (comp (ref "C67")
      (value "100nF")
      (footprint "eagle-import:CAP0603")
      (libsource (lib "eagle-import") (part "CAPACITOR-0603"))
    )
    (comp (ref "C68")
      (value "10pF")
      (footprint "eagle-import:CAP0603")
      (libsource (lib "eagle-import") (part "CAPACITOR-0603"))
    )
    (comp (ref "C69")
      (value "470pF")
      (footprint "eagle-import:CAP0603")
      (libsource (lib "eagle-import") (part "CAPACITOR-0603"))
    )
    (comp (ref "C70")
      (value "100uF")
      (footprint "eagle-import:CAP1206")
      (libsource (lib "eagle-import") (part "CAPACITOR-1206"))
    )
    (comp (ref "C71")
      (value "100uF")
      (footprint "eagle-import:CAP1206")
      (libsource (lib "eagle-import") (part "CAPACITOR-1206"))
    )
    (comp (ref "C72")
      (value "100nF")
      (footprint "eagle-import:CAP0603")
      (libsource (lib "eagle-import") (part "CAPACITOR-0603"))
    )
    (comp (ref "C73")
      (value "1uF")
      (footprint "eagle-import:CAP0603")
      (libsource (lib "eagle-import") (part "CAPACITOR-0603"))
    )
    (comp (ref "C74")
      (value "10uF")
      (footprint "eagle-import:CAP0603")
      (libsource (lib "eagle-import") (part "CAPACITOR-0603"))
    )
    (comp (ref "C75")
      (value "10uF")
      (footprint "eagle-import:CAP1206")
      (fields (field (name "VOLTAGE") "50V"))
      (libsource (lib "eagle-import") (part "CAPACITOR-1206"))
    )
    (comp (ref "C76")
      (value "470pF")
      (footprint "eagle-import:CAP0603")
      (libsource (lib "eagle-import") (part "CAPACITOR-0603"))
    )
    (comp (ref "CON2")
      (value "2EDG-2P-5MM")
      (footprint "eagle-import:2EDG-2P-5MM")
      (libsource (lib "eagle-import") (part "2EDG-2P-5MM"))
    )
    (comp (ref "D4")
      (value "LED0603")
      (footprint "eagle-import:0603")
      (fields (field (name "COLOR") "GREEN"))
      (libsource (lib "eagle-import") (part "LED0603"))
    )
    (comp (ref "D5")
      (value "SMAJ24A")
      (footprint "eagle-import:DO214AC")
      (fields (field (name "MF") "Littelfuse"))
      (libsource (lib "eagle-import") (part "SMAJA24"))
    )
    (comp (ref "F3")
      (value "2.6A Hold")
      (footprint "eagle-import:1206")
      (fields (field (name "HOLD") "3A") (field (name "TRIP") "6A"))
      (libsource (lib "eagle-import") (part "PTC1206"))
    )
    (comp (ref "L19")
      (value "2.2uH")
      (footprint "eagle-import:IND2520")
      (fields (field (name "CURRENT") "2.2A"))
      (libsource (lib "eagle-import") (part "INDUCTOR-2.5X2X1.2MM"))
    )
    (comp (ref "L20")
      (value "4.7uH")
      (footprint "eagle-import:IND2520")
      (fields (field (name "CURRENT") "1.4A"))
      (libsource (lib "eagle-import") (part "INDUCTOR-2.5X2X1.2MM"))
    )
    (comp (ref "R31")
      (value "100K Ohms")
      (footprint "eagle-import:RES0603")
      (libsource (lib "eagle-import") (part "RESISTOR-0603"))
    )
    (comp (ref "R32")
      (value "10K Ohms")
      (footprint "eagle-import:RES0603")
      (libsource (lib "eagle-import") (part "RESISTOR-0603"))
    )
    (comp (ref "R33")
      (value "90.9K Ohms")
      (footprint "eagle-import:RES0603")
      (libsource (lib "eagle-import") (part "RESISTOR-0603"))
    )
    (comp (ref "R34")
      (value "12K Ohms")
      (footprint "eagle-import:RES0603")
      (libsource (lib "eagle-import") (part "RESISTOR-0603"))
    )
    (comp (ref "R35")
      (value "41.2K Ohms")
      (footprint "eagle-import:RES0603")
      (libsource (lib "eagle-import") (part "RESISTOR-0603"))
    )
    (comp (ref "R36")
      (value "309K Ohms")
      (footprint "eagle-import:RES0603")
      (libsource (lib "eagle-import") (part "RESISTOR-0603"))
    )
    (comp (ref "R37")
      (value "71.5K Ohms")
      (footprint "eagle-import:RES0603")
      (libsource (lib "eagle-import") (part "RESISTOR-0603"))
    )
    (comp (ref "R38")
      (value "90.9K Ohms")
      (footprint "eagle-import:RES0603")
      (libsource (lib "eagle-import") (part "RESISTOR-0603"))
    )
    (comp (ref "R39")
      (value "12K Ohms")
      (footprint "eagle-import:RES0603")
      (libsource (lib "eagle-import") (part "RESISTOR-0603"))
    )
    (comp (ref "R40")
      (value "1M Ohms")
      (footprint "eagle-import:RES0603")
      (libsource (lib "eagle-import") (part "RESISTOR-0603"))
    )
    (comp (ref "R41")
      (value "226K Ohms")
      (footprint "eagle-import:RES0603")
      (libsource (lib "eagle-import") (part "RESISTOR-0603"))
    )
    (comp (ref "R42")
      (value "510 Ohms")
      (footprint "eagle-import:RES0603")
      (libsource (lib "eagle-import") (part "RESISTOR-0603"))
    )
    (comp (ref "R43")
      (value "75K Ohms")
      (footprint "eagle-import:RES0603")
      (libsource (lib "eagle-import") (part "RESISTOR-0603"))
    )
    (comp (ref "R44")
      (value "100K Ohms")
      (footprint "eagle-import:RES0603")
      (libsource (lib "eagle-import") (part "RESISTOR-0603"))
    )
    (comp (ref "U6")
      (value "MIC23155")
      (footprint "eagle-import:DFN10")
      (libsource (lib "eagle-import") (part "MIC23155"))
    )
    (comp (ref "U7")
      (value "LT8636")
      (footprint "eagle-import:QFN20_ASYM_CORNER")
      (libsource (lib "eagle-import") (part "LT8636"))
    )
    (comp (ref "U8")
      (value "ADP7142AUJZ-3.3")
      (footprint "eagle-import:SOT23-5")
      (libsource (lib "eagle-import") (part "ADP7142AUJZ-3.3"))
    )
    (comp (ref "C5")
      (value "100nF")
      (footprint "eagle-import:CAP0603")
      (libsource (lib "eagle-import") (part "CAPACITOR-0603"))
    )
    (comp (ref "C6")
      (value "100nF")
      (footprint "eagle-import:CAP0603")
      (libsource (lib "eagle-import") (part "CAPACITOR-0603"))
    )
    (comp (ref "C7")
      (value "150pF")
      (footprint "eagle-import:CAP0603")
      (libsource (lib "eagle-import") (part "CAPACITOR-0603"))
    )
    (comp (ref "C8")
      (value "150pF")
      (footprint "eagle-import:CAP0603")
      (libsource (lib "eagle-import") (part "CAPACITOR-0603"))
    )
    (comp (ref "C9")
      (value "100nF")
      (footprint "eagle-import:CAP0603")
      (libsource (lib "eagle-import") (part "CAPACITOR-0603"))
    )
    (comp (ref "C10")
      (value "100nF")
      (footprint "eagle-import:CAP0603")
      (libsource (lib "eagle-import") (part "CAPACITOR-0603"))
    )
    (comp (ref "C11")
      (value "330pF")
      (footprint "eagle-import:CAP0603")
      (libsource (lib "eagle-import") (part "CAPACITOR-0603"))
    )
    (comp (ref "C12")
      (value "330pF")
      (footprint "eagle-import:CAP0603")
      (libsource (lib "eagle-import") (part "CAPACITOR-0603"))
    )
    (comp (ref "C13")
      (value "100pF")
      (footprint "eagle-import:CAP0603")
      (libsource (lib "eagle-import") (part "CAPACITOR-0603"))
    )
    (comp (ref "C14")
      (value "100pF")
      (footprint "eagle-import:CAP0603")
      (libsource (lib "eagle-import") (part "CAPACITOR-0603"))
    )
    (comp (ref "C15")
      (value "100pF")
      (footprint "eagle-import:CAP0603")
      (libsource (lib "eagle-import") (part "CAPACITOR-0603"))
    )
    (comp (ref "C16")
      (value "100pF")
      (footprint "eagle-import:CAP0603")
      (libsource (lib "eagle-import") (part "CAPACITOR-0603"))
    )
    (comp (ref "C17")
      (value "1nF")
      (footprint "eagle-import:CAP0603")
      (libsource (lib "eagle-import") (part "CAPACITOR-0603"))
    )
    (comp (ref "C18")
      (value "1nF")
      (footprint "eagle-import:CAP0603")
      (libsource (lib "eagle-import") (part "CAPACITOR-0603"))
    )
    (comp (ref "C19")
      (value "330pF")
      (footprint "eagle-import:CAP0603")
      (libsource (lib "eagle-import") (part "CAPACITOR-0603"))
    )
    (comp (ref "C20")
      (value "330pF")
      (footprint "eagle-import:CAP0603")
      (libsource (lib "eagle-import") (part "CAPACITOR-0603"))
    )
    (comp (ref "C21")
      (value "100pF")
      (footprint "eagle-import:CAP0603")
      (libsource (lib "eagle-import") (part "CAPACITOR-0603"))
    )
    (comp (ref "C22")
      (value "100pF")
      (footprint "eagle-import:CAP0603")
      (libsource (lib "eagle-import") (part "CAPACITOR-0603"))
    )
    (comp (ref "C23")
      (value "68pF")
      (footprint "eagle-import:CAP0603")
      (libsource (lib "eagle-import") (part "CAPACITOR-0603"))
    )
    (comp (ref "C24")
      (value "68pF")
      (footprint "eagle-import:CAP0603")
      (libsource (lib "eagle-import") (part "CAPACITOR-0603"))
    )
    (comp (ref "L1")
      (value "470nH")
      (footprint "eagle-import:IND0603")
      (fields (field (name "CURRENT") "600 mA"))
      (libsource (lib "eagle-import") (part "INDUCTOR-0603"))
    )
    (comp (ref "L2")
      (value "470nH")
      (footprint "eagle-import:IND0603")
      (fields (field (name "CURRENT") "600 mA"))
      (libsource (lib "eagle-import") (part "INDUCTOR-0603"))
    )
    (comp (ref "L3")
      (value "470nH")
      (footprint "eagle-import:IND0603")
      (fields (field (name "CURRENT") "600 mA"))
      (libsource (lib "eagle-import") (part "INDUCTOR-0603"))
    )
    (comp (ref "L4")
      (value "470nH")
      (footprint "eagle-import:IND0603")
      (fields (field (name "CURRENT") "600 mA"))
      (libsource (lib "eagle-import") (part "INDUCTOR-0603"))
    )
    (comp (ref "L5")
      (value "470nH")
      (footprint "eagle-import:IND0603")
      (libsource (lib "eagle-import") (part "INDUCTOR-0603"))
    )
    (comp (ref "L6")
      (value "470nH")
      (footprint "eagle-import:IND0603")
      (libsource (lib "eagle-import") (part "INDUCTOR-0603"))
    )
    (comp (ref "L7")
      (value "120nH")
      (footprint "eagle-import:IND0603")
      (libsource (lib "eagle-import") (part "INDUCTOR-0603"))
    )
    (comp (ref "L8")
      (value "120nH")
      (footprint "eagle-import:IND0603")
      (libsource (lib "eagle-import") (part "INDUCTOR-0603"))
    )
    (comp (ref "L9")
      (value "43nH")
      (footprint "eagle-import:IND0603")
      (libsource (lib "eagle-import") (part "INDUCTOR-0603"))
    )
    (comp (ref "L10")
      (value "330nH")
      (footprint "eagle-import:IND0603")
      (libsource (lib "eagle-import") (part "INDUCTOR-0603"))
    )
    (comp (ref "L11")
      (value "43nH")
      (footprint "eagle-import:IND0603")
      (libsource (lib "eagle-import") (part "INDUCTOR-0603"))
    )
    (comp (ref "L12")
      (value "330nH")
      (footprint "eagle-import:IND0603")
      (libsource (lib "eagle-import") (part "INDUCTOR-0603"))
    )
    (comp (ref "L13")
      (value "470nH")
      (footprint "eagle-import:IND0603")
      (libsource (lib "eagle-import") (part "INDUCTOR-0603"))
    )
    (comp (ref "L14")
      (value "120nH")
      (footprint "eagle-import:IND0603")
      (libsource (lib "eagle-import") (part "INDUCTOR-0603"))
    )
    (comp (ref "L15")
      (value "470nH")
      (footprint "eagle-import:IND0603")
      (libsource (lib "eagle-import") (part "INDUCTOR-0603"))
    )
    (comp (ref "L16")
      (value "120nH")
      (footprint "eagle-import:IND0603")
      (libsource (lib "eagle-import") (part "INDUCTOR-0603"))
    )
    (comp (ref "R7")
      (value "43.2 Ohms")
      (footprint "eagle-import:RES0603")
      (libsource (lib "eagle-import") (part "RESISTOR-0603"))
    )
    (comp (ref "R8")
      (value "43.2 Ohms")
      (footprint "eagle-import:RES0603")
      (libsource (lib "eagle-import") (part "RESISTOR-0603"))
    )
    (comp (ref "R9")
      (value "86.6 Ohms")
      (footprint "eagle-import:RES0603")
      (libsource (lib "eagle-import") (part "RESISTOR-0603"))
    )
    (comp (ref "R10")
      (value "86.6 Ohms")
      (footprint "eagle-import:RES0603")
      (libsource (lib "eagle-import") (part "RESISTOR-0603"))
    )
    (comp (ref "RFCON1")
      (value "RFCON-F-EDGE")
      (footprint "eagle-import:F-EDGE")
      (libsource (lib "eagle-import") (part "RFCON-F-EDGE"))
    )
    (comp (ref "RFCON2")
      (value "RFCON-F-EDGE")
      (footprint "eagle-import:F-EDGE")
      (libsource (lib "eagle-import") (part "RFCON-F-EDGE"))
    )
    (comp (ref "RFCON3")
      (value "RFCON-SMA-EDGE")
      (footprint "eagle-import:SMA-EDGE")
      (libsource (lib "eagle-import") (part "RFCON-SMA-EDGE"))
    )
    (comp (ref "RFCON4")
      (value "RFCON-SMA-EDGE")
      (footprint "eagle-import:SMA-EDGE")
      (libsource (lib "eagle-import") (part "RFCON-SMA-EDGE"))
    )
    (comp (ref "C25")
      (value "100nF")
      (footprint "eagle-import:CAP0603")
      (libsource (lib "eagle-import") (part "CAPACITOR-0603"))
    )
    (comp (ref "C26")
      (value "100nF")
      (footprint "eagle-import:CAP0603")
      (libsource (lib "eagle-import") (part "CAPACITOR-0603"))
    )
    (comp (ref "C27")
      (value "10pF")
      (footprint "eagle-import:CAP0603")
      (libsource (lib "eagle-import") (part "CAPACITOR-0603"))
    )
    (comp (ref "C28")
      (value "10pF")
      (footprint "eagle-import:CAP0603")
      (libsource (lib "eagle-import") (part "CAPACITOR-0603"))
    )
    (comp (ref "C29")
      (value "100nF")
      (footprint "eagle-import:CAP0603")
      (libsource (lib "eagle-import") (part "CAPACITOR-0603"))
    )
    (comp (ref "C30")
      (value "100nF")
      (footprint "eagle-import:CAP0603")
      (libsource (lib "eagle-import") (part "CAPACITOR-0603"))
    )
    (comp (ref "R11")
      (value "100K Ohms")
      (footprint "eagle-import:RES0603")
      (libsource (lib "eagle-import") (part "RESISTOR-0603"))
    )
    (comp (ref "R12")
      (value "10K Ohms")
      (footprint "eagle-import:RES0603")
      (libsource (lib "eagle-import") (part "RESISTOR-0603"))
    )
    (comp (ref "R13")
      (value "0 Ohms")
      (footprint "eagle-import:RES0603")
      (libsource (lib "eagle-import") (part "RESISTOR-0603"))
    )
    (comp (ref "R14")
      (value "0 Ohms")
      (footprint "eagle-import:RES0603")
      (libsource (lib "eagle-import") (part "RESISTOR-0603"))
    )
    (comp (ref "R15")
      (value "0 Ohms")
      (footprint "eagle-import:RES0603")
      (libsource (lib "eagle-import") (part "RESISTOR-0603"))
    )
    (comp (ref "R16")
      (value "0 Ohms")
      (footprint "eagle-import:RES0603")
      (libsource (lib "eagle-import") (part "RESISTOR-0603"))
    )
    (comp (ref "RFCON5")
      (value "RFCON-U.FL")
      (footprint "eagle-import:U.FL")
      (libsource (lib "eagle-import") (part "RFCON-U.FL"))
    )
    (comp (ref "RFCON6")
      (value "RFCON-U.FL")
      (footprint "eagle-import:U.FL")
      (libsource (lib "eagle-import") (part "RFCON-U.FL"))
    )
    (comp (ref "U2")
      (value "DSB321SDA")
      (footprint "eagle-import:TCXO-3225")
      (libsource (lib "eagle-import") (part "DSB321SDA"))
    )
    (comp (ref "U3")
      (value "SI5351C-B-GM")
      (footprint "eagle-import:QFN20")
      (libsource (lib "eagle-import") (part "SI5351C-B-GM"))
    )
  )
  (nets
    (net (code "1") (name "3V3") (class "Default")
      (node (ref "C1") (pin "1") (pinfunction "C1_1") (pintype "passive"))
      (node (ref "C2") (pin "1") (pinfunction "C1_1") (pintype "passive"))
      (node (ref "C3") (pin "1") (pinfunction "C1_1") (pintype "passive"))
      (node (ref "C48") (pin "1") (pinfunction "C1_1") (pintype "passive"))
      (node (ref "C50") (pin "1") (pinfunction "C1_1") (pintype "passive"))
      (node (ref "C66") (pin "1") (pinfunction "C1_1") (pintype "passive"))
      (node (ref "C70") (pin "1") (pinfunction "C1_1") (pintype "passive"))
      (node (ref "L19") (pin "2") (pinfunction "2_2") (pintype "passive"))
      (node (ref "R1") (pin "2") (pinfunction "2_2") (pintype "passive"))
      (node (ref "R11") (pin "2") (pinfunction "2_2") (pintype "passive"))
      (node (ref "R2") (pin "2") (pinfunction "2_2") (pintype "passive"))
      (node (ref "R20") (pin "2") (pinfunction "2_2") (pintype "passive"))
      (node (ref "R21") (pin "2") (pinfunction "2_2") (pintype "passive"))
      (node (ref "R3") (pin "2") (pinfunction "2_2") (pintype "passive"))
      (node (ref "R36") (pin "2") (pinfunction "2_2") (pintype "passive"))
      (node (ref "R45") (pin "2") (pinfunction "2_2") (pintype "passive"))
      (node (ref "R46") (pin "2") (pinfunction "2_2") (pintype "passive"))
      (node (ref "TC1") (pin "1") (pinfunction "S_1") (pintype "passive"))
      (node (ref "U1") (pin "11") (pinfunction "AVDD_11") (pintype "bidirectional"))
      (node (ref "U1") (pin "14") (pinfunction "IOVDD0_14") (pintype "bidirectional"))
      (node (ref "U1") (pin "15") (pinfunction "AVDD_15") (pintype "bidirectional"))
      (node (ref "U1") (pin "20") (pinfunction "DVDD_20") (pintype "bidirectional"))
      (node (ref "U1") (pin "28") (pinfunction "IOVDD0_28") (pintype "bidirectional"))
      (node (ref "U1") (pin "4") (pinfunction "IOVDD0_4") (pintype "bidirectional"))
      (node (ref "U5") (pin "1") (pinfunction "VDD_1") (pintype "bidirectional"))
      (node (ref "U5") (pin "4") (pinfunction "~{LDAC}_4") (pintype "bidirectional"))
      (node (ref "U6") (pin "3") (pinfunction "SNS_3") (pintype "bidirectional"))
    )
    (net (code "2") (name "3V3_REF_CLEAN") (class "Default")
      (node (ref "C25") (pin "1") (pinfunction "C1_1") (pintype "passive"))
      (node (ref "C26") (pin "1") (pinfunction "C1_1") (pintype "passive"))
      (node (ref "C29") (pin "1") (pinfunction "C1_1") (pintype "passive"))
      (node (ref "C30") (pin "1") (pinfunction "C1_1") (pintype "passive"))
      (node (ref "C74") (pin "1") (pinfunction "C1_1") (pintype "passive"))
      (node (ref "U2") (pin "4") (pinfunction "VDD_4") (pintype "power_in"))
      (node (ref "U3") (pin "10") (pinfunction "VDDOB_10") (pintype "bidirectional"))
      (node (ref "U3") (pin "11") (pinfunction "VDDOA_11") (pintype "bidirectional"))
      (node (ref "U3") (pin "14") (pinfunction "VDDOD_14") (pintype "bidirectional"))
      (node (ref "U3") (pin "18") (pinfunction "VDDOC_18") (pintype "bidirectional"))
      (node (ref "U3") (pin "20") (pinfunction "VDD_20") (pintype "bidirectional"))
      (node (ref "U8") (pin "4") (pinfunction "SENSE/ADJ_4") (pintype "bidirectional"))
      (node (ref "U8") (pin "5") (pinfunction "VOUT_5") (pintype "bidirectional"))
    )
    (net (code "3") (name "5V0") (class "Default")
      (node (ref "C58") (pin "1") (pinfunction "C1_1") (pintype "passive"))
      (node (ref "C68") (pin "1") (pinfunction "C1_1") (pintype "passive"))
      (node (ref "C71") (pin "1") (pinfunction "C1_1") (pintype "passive"))
      (node (ref "C72") (pin "1") (pinfunction "C1_1") (pintype "passive"))
      (node (ref "C73") (pin "1") (pinfunction "C1_1") (pintype "passive"))
      (node (ref "L20") (pin "2") (pinfunction "2_2") (pintype "passive"))
      (node (ref "R40") (pin "2") (pinfunction "2_2") (pintype "passive"))
      (node (ref "R42") (pin "2") (pinfunction "2_2") (pintype "passive"))
      (node (ref "R44") (pin "2") (pinfunction "2_2") (pintype "passive"))
      (node (ref "U4") (pin "22") (pinfunction "BIAS_22") (pintype "bidirectional"))
      (node (ref "U6") (pin "2") (pinfunction "EN_2") (pintype "bidirectional"))
      (node (ref "U6") (pin "8") (pinfunction "VIN_8") (pintype "bidirectional"))
      (node (ref "U6") (pin "9") (pinfunction "VIN_9") (pintype "bidirectional"))
      (node (ref "U7") (pin "2") (pinfunction "BIAS_2") (pintype "bidirectional"))
      (node (ref "U8") (pin "1") (pinfunction "VIN_1") (pintype "bidirectional"))
      (node (ref "U8") (pin "3") (pinfunction "EN_3") (pintype "bidirectional"))
    )
    (net (code "4") (name "5V0_VSENSE") (class "Default")
      (node (ref "C76") (pin "1") (pinfunction "C1_1") (pintype "passive"))
      (node (ref "R43") (pin "2") (pinfunction "2_2") (pintype "passive"))
      (node (ref "R44") (pin "1") (pinfunction "1_1") (pintype "passive"))
      (node (ref "U1") (pin "12") (pinfunction "PB13_12") (pintype "bidirectional"))
    )
    (net (code "5") (name "BIAS_REG_TEMP") (class "Default")
      (node (ref "C34") (pin "1") (pinfunction "C1_1") (pintype "passive"))
      (node (ref "R22") (pin "1") (pinfunction "1_1") (pintype "passive"))
      (node (ref "U1") (pin "1") (pinfunction "PA0_1") (pintype "bidirectional"))
    )
    (net (code "6") (name "GND") (class "Default")
      (node (ref "C1") (pin "2") (pinfunction "C2_2") (pintype "passive"))
      (node (ref "C17") (pin "2") (pinfunction "C2_2") (pintype "passive"))
      (node (ref "C18") (pin "2") (pinfunction "C2_2") (pintype "passive"))
      (node (ref "C2") (pin "2") (pinfunction "C2_2") (pintype "passive"))
      (node (ref "C25") (pin "2") (pinfunction "C2_2") (pintype "passive"))
      (node (ref "C26") (pin "2") (pinfunction "C2_2") (pintype "passive"))
      (node (ref "C27") (pin "2") (pinfunction "C2_2") (pintype "passive"))
      (node (ref "C29") (pin "2") (pinfunction "C2_2") (pintype "passive"))
      (node (ref "C3") (pin "2") (pinfunction "C2_2") (pintype "passive"))
      (node (ref "C30") (pin "2") (pinfunction "C2_2") (pintype "passive"))
      (node (ref "C31") (pin "2") (pinfunction "C2_2") (pintype "passive"))
      (node (ref "C32") (pin "2") (pinfunction "C2_2") (pintype "passive"))
      (node (ref "C33") (pin "2") (pinfunction "C2_2") (pintype "passive"))
      (node (ref "C34") (pin "2") (pinfunction "C2_2") (pintype "passive"))
      (node (ref "C37") (pin "2") (pinfunction "C2_2") (pintype "passive"))
      (node (ref "C4") (pin "2") (pinfunction "C2_2") (pintype "passive"))
      (node (ref "C40") (pin "2") (pinfunction "C2_2") (pintype "passive"))
      (node (ref "C41") (pin "2") (pinfunction "C2_2") (pintype "passive"))
      (node (ref "C42") (pin "2") (pinfunction "C2_2") (pintype "passive"))
      (node (ref "C43") (pin "2") (pinfunction "C2_2") (pintype "passive"))
      (node (ref "C44") (pin "2") (pinfunction "C2_2") (pintype "passive"))
      (node (ref "C45") (pin "2") (pinfunction "C2_2") (pintype "passive"))
      (node (ref "C46") (pin "2") (pinfunction "C2_2") (pintype "passive"))
      (node (ref "C47") (pin "2") (pinfunction "C2_2") (pintype "passive"))
      (node (ref "C48") (pin "2") (pinfunction "C2_2") (pintype "passive"))
      (node (ref "C49") (pin "2") (pinfunction "C2_2") (pintype "passive"))
      (node (ref "C5") (pin "2") (pinfunction "C2_2") (pintype "passive"))
      (node (ref "C50") (pin "2") (pinfunction "C2_2") (pintype "passive"))
      (node (ref "C51") (pin "2") (pinfunction "C2_2") (pintype "passive"))
      (node (ref "C52") (pin "2") (pinfunction "C2_2") (pintype "passive"))
      (node (ref "C53") (pin "2") (pinfunction "C2_2") (pintype "passive"))
      (node (ref "C54") (pin "2") (pinfunction "C2_2") (pintype "passive"))
      (node (ref "C55") (pin "2") (pinfunction "C2_2") (pintype "passive"))
      (node (ref "C56") (pin "2") (pinfunction "C2_2") (pintype "passive"))
      (node (ref "C57") (pin "2") (pinfunction "C2_2") (pintype "passive"))
      (node (ref "C58") (pin "2") (pinfunction "C2_2") (pintype "passive"))
      (node (ref "C59") (pin "2") (pinfunction "C2_2") (pintype "passive"))
      (node (ref "C6") (pin "2") (pinfunction "C2_2") (pintype "passive"))
      (node (ref "C60") (pin "2") (pinfunction "C2_2") (pintype "passive"))
      (node (ref "C61") (pin "2") (pinfunction "C2_2") (pintype "passive"))
      (node (ref "C62") (pin "2") (pinfunction "C2_2") (pintype "passive"))
      (node (ref "C63") (pin "2") (pinfunction "C2_2") (pintype "passive"))
      (node (ref "C64") (pin "2") (pinfunction "C2_2") (pintype "passive"))
      (node (ref "C65") (pin "2") (pinfunction "C2_2") (pintype "passive"))
      (node (ref "C66") (pin "2") (pinfunction "C2_2") (pintype "passive"))
      (node (ref "C69") (pin "2") (pinfunction "C2_2") (pintype "passive"))
      (node (ref "C7") (pin "2") (pinfunction "C2_2") (pintype "passive"))
      (node (ref "C70") (pin "2") (pinfunction "C2_2") (pintype "passive"))
      (node (ref "C71") (pin "2") (pinfunction "C2_2") (pintype "passive"))
      (node (ref "C72") (pin "2") (pinfunction "C2_2") (pintype "passive"))
      (node (ref "C73") (pin "2") (pinfunction "C2_2") (pintype "passive"))
      (node (ref "C74") (pin "2") (pinfunction "C2_2") (pintype "passive"))
      (node (ref "C75") (pin "2") (pinfunction "C2_2") (pintype "passive"))
      (node (ref "C76") (pin "2") (pinfunction "C2_2") (pintype "passive"))
      (node (ref "C8") (pin "2") (pinfunction "C2_2") (pintype "passive"))
      (node (ref "CON1") (pin "3") (pinfunction "S_3") (pintype "passive"))
      (node (ref "CON2") (pin "P$1") (pinfunction "S_P$1") (pintype "passive"))
      (node (ref "D1") (pin "C") (pinfunction "C_C") (pintype "passive"))
      (node (ref "D2") (pin "C") (pinfunction "C_C") (pintype "passive"))
      (node (ref "D3") (pin "C") (pinfunction "C_C") (pintype "passive"))
      (node (ref "D4") (pin "C") (pinfunction "C_C") (pintype "passive"))
      (node (ref "D5") (pin "A") (pinfunction "A_A") (pintype "passive"))
      (node (ref "L10") (pin "1") (pinfunction "1_1") (pintype "passive"))
      (node (ref "L11") (pin "2") (pinfunction "2_2") (pintype "passive"))
      (node (ref "L12") (pin "1") (pinfunction "1_1") (pintype "passive"))
      (node (ref "L9") (pin "2") (pinfunction "2_2") (pintype "passive"))
      (node (ref "R10") (pin "1") (pinfunction "1_1") (pintype "passive"))
      (node (ref "R12") (pin "1") (pinfunction "1_1") (pintype "passive"))
      (node (ref "R17") (pin "1") (pinfunction "1_1") (pintype "passive"))
      (node (ref "R18") (pin "1") (pinfunction "1_1") (pintype "passive"))
      (node (ref "R19") (pin "1") (pinfunction "1_1") (pintype "passive"))
      (node (ref "R26") (pin "1") (pinfunction "1_1") (pintype "passive"))
      (node (ref "R28") (pin "1") (pinfunction "1_1") (pintype "passive"))
      (node (ref "R32") (pin "1") (pinfunction "1_1") (pintype "passive"))
      (node (ref "R34") (pin "1") (pinfunction "1_1") (pintype "passive"))
      (node (ref "R35") (pin "1") (pinfunction "1_1") (pintype "passive"))
      (node (ref "R37") (pin "1") (pinfunction "1_1") (pintype "passive"))
      (node (ref "R39") (pin "1") (pinfunction "1_1") (pintype "passive"))
      (node (ref "R41") (pin "1") (pinfunction "1_1") (pintype "passive"))
      (node (ref "R43") (pin "1") (pinfunction "1_1") (pintype "passive"))
      (node (ref "R9") (pin "1") (pinfunction "1_1") (pintype "passive"))
      (node (ref "RFCON1") (pin "GND@0") (pinfunction "GND_GND@0") (pintype "bidirectional"))
      (node (ref "RFCON1") (pin "GND@1") (pinfunction "GND_GND@1") (pintype "bidirectional"))
      (node (ref "RFCON1") (pin "GND@2") (pinfunction "GND_GND@2") (pintype "bidirectional"))
      (node (ref "RFCON1") (pin "GND@3") (pinfunction "GND_GND@3") (pintype "bidirectional"))
      (node (ref "RFCON1") (pin "GND@4") (pinfunction "GND_GND@4") (pintype "bidirectional"))
      (node (ref "RFCON1") (pin "GND@5") (pinfunction "GND_GND@5") (pintype "bidirectional"))
      (node (ref "RFCON2") (pin "GND@0") (pinfunction "GND_GND@0") (pintype "bidirectional"))
      (node (ref "RFCON2") (pin "GND@1") (pinfunction "GND_GND@1") (pintype "bidirectional"))
      (node (ref "RFCON2") (pin "GND@2") (pinfunction "GND_GND@2") (pintype "bidirectional"))
      (node (ref "RFCON2") (pin "GND@3") (pinfunction "GND_GND@3") (pintype "bidirectional"))
      (node (ref "RFCON2") (pin "GND@4") (pinfunction "GND_GND@4") (pintype "bidirectional"))
      (node (ref "RFCON2") (pin "GND@5") (pinfunction "GND_GND@5") (pintype "bidirectional"))
      (node (ref "RFCON3") (pin "GND@0") (pinfunction "GND_GND@0") (pintype "bidirectional"))
      (node (ref "RFCON3") (pin "GND@1") (pinfunction "GND_GND@1") (pintype "bidirectional"))
      (node (ref "RFCON3") (pin "GND@2") (pinfunction "GND_GND@2") (pintype "bidirectional"))
      (node (ref "RFCON3") (pin "GND@3") (pinfunction "GND_GND@3") (pintype "bidirectional"))
      (node (ref "RFCON4") (pin "GND@0") (pinfunction "GND_GND@0") (pintype "bidirectional"))
      (node (ref "RFCON4") (pin "GND@1") (pinfunction "GND_GND@1") (pintype "bidirectional"))
      (node (ref "RFCON4") (pin "GND@2") (pinfunction "GND_GND@2") (pintype "bidirectional"))
      (node (ref "RFCON4") (pin "GND@3") (pinfunction "GND_GND@3") (pintype "bidirectional"))
      (node (ref "RFCON5") (pin "P$1") (pinfunction "GND_P$1") (pintype "bidirectional"))
      (node (ref "RFCON5") (pin "P$2") (pinfunction "GND_P$2") (pintype "bidirectional"))
      (node (ref "RFCON6") (pin "P$1") (pinfunction "GND_P$1") (pintype "bidirectional"))
      (node (ref "RFCON6") (pin "P$2") (pinfunction "GND_P$2") (pintype "bidirectional"))
      (node (ref "TC1") (pin "3") (pinfunction "S_3") (pintype "passive"))
      (node (ref "U1") (pin "33") (pinfunction "VSS_33") (pintype "bidirectional"))
      (node (ref "U2") (pin "1") (pinfunction "GND_1") (pintype "power_in"))
      (node (ref "U2") (pin "2") (pinfunction "GND_2") (pintype "power_in"))
      (node (ref "U3") (pin "21") (pinfunction "GND_21") (pintype "bidirectional"))
      (node (ref "U4") (pin "2") (pinfunction "GND_2") (pintype "bidirectional"))
      (node (ref "U4") (pin "29") (pinfunction "GND_29") (pintype "bidirectional"))
      (node (ref "U4") (pin "30") (pinfunction "GND_30") (pintype "bidirectional"))
      (node (ref "U4") (pin "31") (pinfunction "GND_31") (pintype "bidirectional"))
      (node (ref "U4") (pin "32") (pinfunction "GND_32") (pintype "bidirectional"))
      (node (ref "U4") (pin "33") (pinfunction "GND_33") (pintype "bidirectional"))
      (node (ref "U4") (pin "34") (pinfunction "GND_34") (pintype "bidirectional"))
      (node (ref "U4") (pin "35") (pinfunction "GND_35") (pintype "bidirectional"))
      (node (ref "U4") (pin "36") (pinfunction "GND_36") (pintype "bidirectional"))
      (node (ref "U4") (pin "37") (pinfunction "GND_37") (pintype "bidirectional"))
      (node (ref "U4") (pin "38") (pinfunction "GND_38") (pintype "bidirectional"))
      (node (ref "U4") (pin "7") (pinfunction "GND_7") (pintype "bidirectional"))
      (node (ref "U5") (pin "10") (pinfunction "VSS_10") (pintype "bidirectional"))
      (node (ref "U6") (pin "10") (pinfunction "PGND_10") (pintype "bidirectional"))
      (node (ref "U6") (pin "11") (pinfunction "PGND_11") (pintype "bidirectional"))
      (node (ref "U6") (pin "7") (pinfunction "AGND_7") (pintype "bidirectional"))
      (node (ref "U7") (pin "12") (pinfunction "GND_12") (pintype "bidirectional"))
      (node (ref "U7") (pin "13") (pinfunction "GND_13") (pintype "bidirectional"))
      (node (ref "U7") (pin "21") (pinfunction "GND_21") (pintype "bidirectional"))
      (node (ref "U7") (pin "4") (pinfunction "GND_4") (pintype "bidirectional"))
      (node (ref "U7") (pin "5") (pinfunction "GND_5") (pintype "bidirectional"))
      (node (ref "U7") (pin "M1") (pinfunction "GND_M1") (pintype "bidirectional"))
      (node (ref "U7") (pin "M2") (pinfunction "GND_M2") (pintype "bidirectional"))
      (node (ref "U7") (pin "M3") (pinfunction "GND_M3") (pintype "bidirectional"))
      (node (ref "U7") (pin "M4") (pinfunction "GND_M4") (pintype "bidirectional"))
      (node (ref "U8") (pin "2") (pinfunction "GND_2") (pintype "bidirectional"))
    )
    (net (code "7") (name "I2C0_SCL") (class "Default")
      (node (ref "R46") (pin "1") (pinfunction "1_1") (pintype "passive"))
      (node (ref "R5") (pin "2") (pinfunction "2_2") (pintype "passive"))
      (node (ref "U1") (pin "19") (pinfunction "PD7_19") (pintype "bidirectional"))
    )
    (net (code "8") (name "I2C0_SDA") (class "Default")
      (node (ref "R4") (pin "2") (pinfunction "2_2") (pintype "passive"))
      (node (ref "R45") (pin "1") (pinfunction "1_1") (pintype "passive"))
      (node (ref "U1") (pin "18") (pinfunction "PD6_18") (pintype "bidirectional"))
    )
    (net (code "9") (name "I2C1_SCL") (class "Default")
      (node (ref "R3") (pin "1") (pinfunction "1_1") (pintype "passive"))
      (node (ref "U1") (pin "17") (pinfunction "PD5_17") (pintype "bidirectional"))
      (node (ref "U3") (pin "4") (pinfunction "SCL_4") (pintype "bidirectional"))
      (node (ref "U5") (pin "2") (pinfunction "SCL_2") (pintype "bidirectional"))
    )
    (net (code "10") (name "I2C1_SDA") (class "Default")
      (node (ref "R2") (pin "1") (pinfunction "1_1") (pintype "passive"))
      (node (ref "U1") (pin "16") (pinfunction "PD4_16") (pintype "bidirectional"))
      (node (ref "U3") (pin "5") (pinfunction "SDA_5") (pintype "bidirectional"))
      (node (ref "U5") (pin "3") (pinfunction "SDA_3") (pintype "bidirectional"))
    )
    (net (code "11") (name "LED") (class "Default")
      (node (ref "R6") (pin "2") (pinfunction "2_2") (pintype "passive"))
      (node (ref "U1") (pin "6") (pinfunction "PC1_6") (pintype "bidirectional"))
    )
    (net (code "12") (name "Net-(C4-C1)") (class "Default")
      (node (ref "C4") (pin "1") (pinfunction "C1_1") (pintype "passive"))
      (node (ref "U1") (pin "21") (pinfunction "DECOUPLE_21") (pintype "bidirectional"))
    )
    (net (code "13") (name "Net-(C7-C1)") (class "Default")
      (node (ref "C7") (pin "1") (pinfunction "C1_1") (pintype "passive"))
      (node (ref "L1") (pin "2") (pinfunction "2_2") (pintype "passive"))
      (node (ref "L3") (pin "1") (pinfunction "1_1") (pintype "passive"))
    )
    (net (code "14") (name "Net-(C8-C1)") (class "Default")
      (node (ref "C8") (pin "1") (pinfunction "C1_1") (pintype "passive"))
      (node (ref "L2") (pin "2") (pinfunction "2_2") (pintype "passive"))
      (node (ref "L4") (pin "1") (pinfunction "1_1") (pintype "passive"))
    )
    (net (code "15") (name "Net-(C9-C1)") (class "Default")
      (node (ref "C9") (pin "1") (pinfunction "C1_1") (pintype "passive"))
      (node (ref "L3") (pin "2") (pinfunction "2_2") (pintype "passive"))
      (node (ref "RFCON1") (pin "SIGNAL") (pinfunction "SIGNAL_SIGNAL") (pintype "bidirectional"))
    )
    (net (code "16") (name "Net-(C9-C2)") (class "Default")
      (node (ref "C9") (pin "2") (pinfunction "C2_2") (pintype "passive"))
      (node (ref "R7") (pin "2") (pinfunction "2_2") (pintype "passive"))
    )
    (net (code "17") (name "Net-(C10-C1)") (class "Default")
      (node (ref "C10") (pin "1") (pinfunction "C1_1") (pintype "passive"))
      (node (ref "L4") (pin "2") (pinfunction "2_2") (pintype "passive"))
      (node (ref "RFCON2") (pin "SIGNAL") (pinfunction "SIGNAL_SIGNAL") (pintype "bidirectional"))
    )
    (net (code "18") (name "Net-(C10-C2)") (class "Default")
      (node (ref "C10") (pin "2") (pinfunction "C2_2") (pintype "passive"))
      (node (ref "R8") (pin "2") (pinfunction "2_2") (pintype "passive"))
    )
    (net (code "19") (name "Net-(C11-C1)") (class "Default")
      (node (ref "C11") (pin "1") (pinfunction "C1_1") (pintype "passive"))
      (node (ref "L5") (pin "1") (pinfunction "1_1") (pintype "passive"))
      (node (ref "L7") (pin "1") (pinfunction "1_1") (pintype "passive"))
      (node (ref "R7") (pin "1") (pinfunction "1_1") (pintype "passive"))
      (node (ref "R9") (pin "2") (pinfunction "2_2") (pintype "passive"))
    )
    (net (code "20") (name "Net-(C11-C2)") (class "Default")
      (node (ref "C11") (pin "2") (pinfunction "C2_2") (pintype "passive"))
      (node (ref "C15") (pin "1") (pinfunction "C1_1") (pintype "passive"))
      (node (ref "C19") (pin "1") (pinfunction "C1_1") (pintype "passive"))
      (node (ref "L14") (pin "1") (pinfunction "1_1") (pintype "passive"))
      (node (ref "L7") (pin "2") (pinfunction "2_2") (pintype "passive"))
    )
    (net (code "21") (name "Net-(C12-C1)") (class "Default")
      (node (ref "C12") (pin "1") (pinfunction "C1_1") (pintype "passive"))
      (node (ref "L6") (pin "1") (pinfunction "1_1") (pintype "passive"))
      (node (ref "L8") (pin "1") (pinfunction "1_1") (pintype "passive"))
      (node (ref "R10") (pin "2") (pinfunction "2_2") (pintype "passive"))
      (node (ref "R8") (pin "1") (pinfunction "1_1") (pintype "passive"))
    )
    (net (code "22") (name "Net-(C12-C2)") (class "Default")
      (node (ref "C12") (pin "2") (pinfunction "C2_2") (pintype "passive"))
      (node (ref "C16") (pin "1") (pinfunction "C1_1") (pintype "passive"))
      (node (ref "C20") (pin "1") (pinfunction "C1_1") (pintype "passive"))
      (node (ref "L16") (pin "1") (pinfunction "1_1") (pintype "passive"))
      (node (ref "L8") (pin "2") (pinfunction "2_2") (pintype "passive"))
    )
    (net (code "23") (name "Net-(C13-C1)") (class "Default")
      (node (ref "C13") (pin "1") (pinfunction "C1_1") (pintype "passive"))
      (node (ref "L5") (pin "2") (pinfunction "2_2") (pintype "passive"))
    )
    (net (code "24") (name "Net-(C13-C2)") (class "Default")
      (node (ref "C13") (pin "2") (pinfunction "C2_2") (pintype "passive"))
      (node (ref "C17") (pin "1") (pinfunction "C1_1") (pintype "passive"))
      (node (ref "L13") (pin "1") (pinfunction "1_1") (pintype "passive"))
      (node (ref "L9") (pin "1") (pinfunction "1_1") (pintype "passive"))
    )
    (net (code "25") (name "Net-(C14-C1)") (class "Default")
      (node (ref "C14") (pin "1") (pinfunction "C1_1") (pintype "passive"))
      (node (ref "L6") (pin "2") (pinfunction "2_2") (pintype "passive"))
    )
    (net (code "26") (name "Net-(C14-C2)") (class "Default")
      (node (ref "C14") (pin "2") (pinfunction "C2_2") (pintype "passive"))
      (node (ref "C18") (pin "1") (pinfunction "C1_1") (pintype "passive"))
      (node (ref "L11") (pin "1") (pinfunction "1_1") (pintype "passive"))
      (node (ref "L15") (pin "1") (pinfunction "1_1") (pintype "passive"))
    )
    (net (code "27") (name "Net-(C15-C2)") (class "Default")
      (node (ref "C15") (pin "2") (pinfunction "C2_2") (pintype "passive"))
      (node (ref "L10") (pin "2") (pinfunction "2_2") (pintype "passive"))
    )
    (net (code "28") (name "Net-(C16-C2)") (class "Default")
      (node (ref "C16") (pin "2") (pinfunction "C2_2") (pintype "passive"))
      (node (ref "L12") (pin "2") (pinfunction "2_2") (pintype "passive"))
    )
    (net (code "29") (name "Net-(C19-C2)") (class "Default")
      (node (ref "C19") (pin "2") (pinfunction "C2_2") (pintype "passive"))
      (node (ref "C23") (pin "1") (pinfunction "C1_1") (pintype "passive"))
      (node (ref "L14") (pin "2") (pinfunction "2_2") (pintype "passive"))
    )
    (net (code "30") (name "Net-(C20-C2)") (class "Default")
      (node (ref "C20") (pin "2") (pinfunction "C2_2") (pintype "passive"))
      (node (ref "C24") (pin "1") (pinfunction "C1_1") (pintype "passive"))
      (node (ref "L16") (pin "2") (pinfunction "2_2") (pintype "passive"))
    )
    (net (code "31") (name "Net-(C21-C1)") (class "Default")
      (node (ref "C21") (pin "1") (pinfunction "C1_1") (pintype "passive"))
      (node (ref "L13") (pin "2") (pinfunction "2_2") (pintype "passive"))
    )
    (net (code "32") (name "Net-(C22-C1)") (class "Default")
      (node (ref "C22") (pin "1") (pinfunction "C1_1") (pintype "passive"))
      (node (ref "L15") (pin "2") (pinfunction "2_2") (pintype "passive"))
    )
    (net (code "33") (name "Net-(C23-C2)") (class "Default")
      (node (ref "C23") (pin "2") (pinfunction "C2_2") (pintype "passive"))
      (node (ref "RFCON3") (pin "SIG") (pinfunction "SIGNAL_SIG") (pintype "bidirectional"))
    )
    (net (code "34") (name "Net-(C24-C2)") (class "Default")
      (node (ref "C24") (pin "2") (pinfunction "C2_2") (pintype "passive"))
      (node (ref "RFCON4") (pin "SIG") (pinfunction "SIGNAL_SIG") (pintype "bidirectional"))
    )
    (net (code "35") (name "Net-(C27-C1)") (class "Default")
      (node (ref "C27") (pin "1") (pinfunction "C1_1") (pintype "passive"))
      (node (ref "C28") (pin "1") (pinfunction "C1_1") (pintype "passive"))
      (node (ref "R12") (pin "2") (pinfunction "2_2") (pintype "passive"))
      (node (ref "U2") (pin "3") (pinfunction "CLK_3") (pintype "output"))
    )
    (net (code "36") (name "Net-(C28-C2)") (class "Default")
      (node (ref "C28") (pin "2") (pinfunction "C2_2") (pintype "passive"))
      (node (ref "U3") (pin "1") (pinfunction "XA_1") (pintype "bidirectional"))
    )
    (net (code "37") (name "Net-(C32-C1)") (class "Default")
      (node (ref "C32") (pin "1") (pinfunction "C1_1") (pintype "passive"))
      (node (ref "U4") (pin "26") (pinfunction "SS_26") (pintype "bidirectional"))
    )
    (net (code "38") (name "Net-(C33-C1)") (class "Default")
      (node (ref "C33") (pin "1") (pinfunction "C1_1") (pintype "passive"))
      (node (ref "U4") (pin "25") (pinfunction "SS_25") (pintype "bidirectional"))
    )
    (net (code "39") (name "Net-(C35-C1)") (class "Default")
      (node (ref "C35") (pin "1") (pinfunction "C1_1") (pintype "passive"))
      (node (ref "L17") (pin "1") (pinfunction "1_1") (pintype "passive"))
      (node (ref "U4") (pin "16") (pinfunction "SW_16") (pintype "bidirectional"))
      (node (ref "U4") (pin "17") (pinfunction "SW_17") (pintype "bidirectional"))
    )
    (net (code "40") (name "Net-(C35-C2)") (class "Default")
      (node (ref "C35") (pin "2") (pinfunction "C2_2") (pintype "passive"))
      (node (ref "U4") (pin "15") (pinfunction "BST_15") (pintype "bidirectional"))
    )
    (net (code "41") (name "Net-(C36-C1)") (class "Default")
      (node (ref "C36") (pin "1") (pinfunction "C1_1") (pintype "passive"))
      (node (ref "L18") (pin "1") (pinfunction "1_1") (pintype "passive"))
      (node (ref "U4") (pin "18") (pinfunction "SW_18") (pintype "bidirectional"))
      (node (ref "U4") (pin "19") (pinfunction "SW_19") (pintype "bidirectional"))
    )
    (net (code "42") (name "Net-(C36-C2)") (class "Default")
      (node (ref "C36") (pin "2") (pinfunction "C2_2") (pintype "passive"))
      (node (ref "U4") (pin "20") (pinfunction "BST_20") (pintype "bidirectional"))
    )
    (net (code "43") (name "Net-(C38-C2)") (class "Default")
      (node (ref "C38") (pin "2") (pinfunction "C2_2") (pintype "passive"))
      (node (ref "R23") (pin "1") (pinfunction "1_1") (pintype "passive"))
      (node (ref "R25") (pin "1") (pinfunction "1_1") (pintype "passive"))
      (node (ref "R26") (pin "2") (pinfunction "2_2") (pintype "passive"))
      (node (ref "U4") (pin "27") (pinfunction "FB_27") (pintype "bidirectional"))
    )
    (net (code "44") (name "Net-(C39-C2)") (class "Default")
      (node (ref "C39") (pin "2") (pinfunction "C2_2") (pintype "passive"))
      (node (ref "R24") (pin "1") (pinfunction "1_1") (pintype "passive"))
      (node (ref "R27") (pin "1") (pinfunction "1_1") (pintype "passive"))
      (node (ref "R28") (pin "2") (pinfunction "2_2") (pintype "passive"))
      (node (ref "U4") (pin "24") (pinfunction "FB_24") (pintype "bidirectional"))
    )
    (net (code "45") (name "Net-(C60-C1)") (class "Default")
      (node (ref "C60") (pin "1") (pinfunction "C1_1") (pintype "passive"))
      (node (ref "U6") (pin "6") (pinfunction "SS_6") (pintype "bidirectional"))
    )
    (net (code "46") (name "Net-(C63-C1)") (class "Default")
      (node (ref "C63") (pin "1") (pinfunction "C1_1") (pintype "passive"))
      (node (ref "U7") (pin "15") (pinfunction "SYNC/MODE_15") (pintype "bidirectional"))
      (node (ref "U7") (pin "3") (pinfunction "INTVCC_3") (pintype "bidirectional"))
    )
    (net (code "47") (name "Net-(C64-C1)") (class "Default")
      (node (ref "C64") (pin "1") (pinfunction "C1_1") (pintype "passive"))
      (node (ref "U7") (pin "18") (pinfunction "TR/SS_18") (pintype "bidirectional"))
    )
    (net (code "48") (name "Net-(C67-C1)") (class "Default")
      (node (ref "C67") (pin "1") (pinfunction "C1_1") (pintype "passive"))
      (node (ref "L20") (pin "1") (pinfunction "1_1") (pintype "passive"))
      (node (ref "U7") (pin "10") (pinfunction "SW_10") (pintype "bidirectional"))
      (node (ref "U7") (pin "8") (pinfunction "SW_8") (pintype "bidirectional"))
      (node (ref "U7") (pin "9") (pinfunction "SW_9") (pintype "bidirectional"))
    )
    (net (code "49") (name "Net-(C67-C2)") (class "Default")
      (node (ref "C67") (pin "2") (pinfunction "C2_2") (pintype "passive"))
      (node (ref "U7") (pin "7") (pinfunction "BST_7") (pintype "bidirectional"))
    )
    (net (code "50") (name "Net-(C68-C2)") (class "Default")
      (node (ref "C68") (pin "2") (pinfunction "C2_2") (pintype "passive"))
      (node (ref "R40") (pin "1") (pinfunction "1_1") (pintype "passive"))
      (node (ref "R41") (pin "2") (pinfunction "2_2") (pintype "passive"))
      (node (ref "U7") (pin "19") (pinfunction "FB_19") (pintype "bidirectional"))
      (node (ref "U7") (pin "20") (pinfunction "FB_20") (pintype "bidirectional"))
    )
    (net (code "51") (name "Net-(CON1A-S)") (class "Default")
      (node (ref "CON1") (pin "1") (pinfunction "S_1") (pintype "passive"))
      (node (ref "R4") (pin "1") (pinfunction "1_1") (pintype "passive"))
    )
    (net (code "52") (name "Net-(CON1B-S)") (class "Default")
      (node (ref "CON1") (pin "2") (pinfunction "S_2") (pintype "passive"))
      (node (ref "R5") (pin "1") (pinfunction "1_1") (pintype "passive"))
    )
    (net (code "53") (name "Net-(CON2B-S)") (class "Default")
      (node (ref "CON2") (pin "P$2") (pinfunction "S_P$2") (pintype "passive"))
      (node (ref "F3") (pin "2") (pinfunction "2_2") (pintype "passive"))
    )
    (net (code "54") (name "Net-(D1-PadA)") (class "Default")
      (node (ref "D1") (pin "A") (pinfunction "A_A") (pintype "passive"))
      (node (ref "R6") (pin "1") (pinfunction "1_1") (pintype "passive"))
    )
    (net (code "55") (name "Net-(D2-PadA)") (class "Default")
      (node (ref "D2") (pin "A") (pinfunction "A_A") (pintype "passive"))
      (node (ref "R29") (pin "1") (pinfunction "1_1") (pintype "passive"))
    )
    (net (code "56") (name "Net-(D3-PadA)") (class "Default")
      (node (ref "D3") (pin "A") (pinfunction "A_A") (pintype "passive"))
      (node (ref "R30") (pin "1") (pinfunction "1_1") (pintype "passive"))
    )
    (net (code "57") (name "Net-(D4-PadA)") (class "Default")
      (node (ref "D4") (pin "A") (pinfunction "A_A") (pintype "passive"))
      (node (ref "R42") (pin "1") (pinfunction "1_1") (pintype "passive"))
    )
    (net (code "58") (name "Net-(RFCON5-SIGNAL)") (class "Default")
      (node (ref "R13") (pin "2") (pinfunction "2_2") (pintype "passive"))
      (node (ref "RFCON5") (pin "P$3") (pinfunction "SIGNAL_P$3") (pintype "bidirectional"))
    )
    (net (code "59") (name "Net-(RFCON6-SIGNAL)") (class "Default")
      (node (ref "R16") (pin "1") (pinfunction "1_1") (pintype "passive"))
      (node (ref "RFCON6") (pin "P$3") (pinfunction "SIGNAL_P$3") (pintype "bidirectional"))
    )
    (net (code "60") (name "Net-(U3-CLK1)") (class "Default")
      (node (ref "R14") (pin "2") (pinfunction "2_2") (pintype "passive"))
      (node (ref "U3") (pin "12") (pinfunction "CLK1_12") (pintype "bidirectional"))
    )
    (net (code "61") (name "Net-(U3-CLK5)") (class "Default")
      (node (ref "R15") (pin "2") (pinfunction "2_2") (pintype "passive"))
      (node (ref "U3") (pin "17") (pinfunction "CLK5_17") (pintype "bidirectional"))
    )
    (net (code "62") (name "Net-(U3-CLK7)") (class "Default")
      (node (ref "R16") (pin "2") (pinfunction "2_2") (pintype "passive"))
      (node (ref "U3") (pin "15") (pinfunction "CLK7_15") (pintype "bidirectional"))
    )
    (net (code "63") (name "Net-(U3-CLKIN)") (class "Default")
      (node (ref "R13") (pin "1") (pinfunction "1_1") (pintype "passive"))
      (node (ref "U3") (pin "6") (pinfunction "CLKIN_6") (pintype "bidirectional"))
    )
    (net (code "64") (name "Net-(U4C-RT)") (class "Default")
      (node (ref "R19") (pin "2") (pinfunction "2_2") (pintype "passive"))
      (node (ref "U4") (pin "1") (pinfunction "RT_1") (pintype "bidirectional"))
    )
    (net (code "65") (name "Net-(U4C-TEMP)") (class "Default")
      (node (ref "R22") (pin "2") (pinfunction "2_2") (pintype "passive"))
      (node (ref "U4") (pin "10") (pinfunction "TEMP_10") (pintype "bidirectional"))
    )
    (net (code "66") (name "Net-(U6-FB)") (class "Default")
      (node (ref "R36") (pin "1") (pinfunction "1_1") (pintype "passive"))
      (node (ref "R37") (pin "2") (pinfunction "2_2") (pintype "passive"))
      (node (ref "U6") (pin "4") (pinfunction "FB_4") (pintype "bidirectional"))
    )
    (net (code "67") (name "Net-(U6-SW)") (class "Default")
      (node (ref "L19") (pin "1") (pinfunction "1_1") (pintype "passive"))
      (node (ref "U6") (pin "1") (pinfunction "SW_1") (pintype "bidirectional"))
    )
    (net (code "68") (name "Net-(U7-RT)") (class "Default")
      (node (ref "R35") (pin "2") (pinfunction "2_2") (pintype "passive"))
      (node (ref "U7") (pin "17") (pinfunction "RT_17") (pintype "bidirectional"))
    )
    (net (code "69") (name "REF1") (class "Default")
      (node (ref "C21") (pin "2") (pinfunction "C2_2") (pintype "passive"))
      (node (ref "R14") (pin "1") (pinfunction "1_1") (pintype "passive"))
    )
    (net (code "70") (name "REF2") (class "Default")
      (node (ref "C22") (pin "2") (pinfunction "C2_2") (pintype "passive"))
      (node (ref "R15") (pin "1") (pinfunction "1_1") (pintype "passive"))
    )
    (net (code "71") (name "SWCLK") (class "Default")
      (node (ref "TC1") (pin "4") (pinfunction "S_4") (pintype "passive"))
      (node (ref "U1") (pin "25") (pinfunction "PF0_25") (pintype "bidirectional"))
    )
    (net (code "72") (name "SWDIO") (class "Default")
      (node (ref "TC1") (pin "2") (pinfunction "S_2") (pintype "passive"))
      (node (ref "U1") (pin "26") (pinfunction "PF1_26") (pintype "bidirectional"))
    )
    (net (code "73") (name "SWO") (class "Default")
      (node (ref "TC1") (pin "6") (pinfunction "S_6") (pintype "passive"))
      (node (ref "U1") (pin "27") (pinfunction "PF2_27") (pintype "bidirectional"))
    )
    (net (code "74") (name "VBIAS1") (class "Default")
      (node (ref "C5") (pin "1") (pinfunction "C1_1") (pintype "passive"))
      (node (ref "C51") (pin "1") (pinfunction "C1_1") (pintype "passive"))
      (node (ref "C53") (pin "1") (pinfunction "C1_1") (pintype "passive"))
      (node (ref "C55") (pin "1") (pinfunction "C1_1") (pintype "passive"))
      (node (ref "F1") (pin "1") (pinfunction "1_1") (pintype "passive"))
      (node (ref "L1") (pin "1") (pinfunction "1_1") (pintype "passive"))
      (node (ref "R29") (pin "2") (pinfunction "2_2") (pintype "passive"))
      (node (ref "R33") (pin "2") (pinfunction "2_2") (pintype "passive"))
    )
    (net (code "75") (name "VBIAS1_EN") (class "Default")
      (node (ref "R17") (pin "2") (pinfunction "2_2") (pintype "passive"))
      (node (ref "U1") (pin "31") (pinfunction "PE12_31") (pintype "bidirectional"))
      (node (ref "U4") (pin "9") (pinfunction "EN/UV_9") (pintype "bidirectional"))
    )
    (net (code "76") (name "VBIAS1_PG") (class "Default")
      (node (ref "R20") (pin "1") (pinfunction "1_1") (pintype "passive"))
      (node (ref "U1") (pin "29") (pinfunction "PE10_29") (pintype "bidirectional"))
      (node (ref "U4") (pin "12") (pinfunction "PG_12") (pintype "bidirectional"))
    )
    (net (code "77") (name "VBIAS1_UNFUSED") (class "Default")
      (node (ref "C38") (pin "1") (pinfunction "C1_1") (pintype "passive"))
      (node (ref "C41") (pin "1") (pinfunction "C1_1") (pintype "passive"))
      (node (ref "C43") (pin "1") (pinfunction "C1_1") (pintype "passive"))
      (node (ref "C45") (pin "1") (pinfunction "C1_1") (pintype "passive"))
      (node (ref "C47") (pin "1") (pinfunction "C1_1") (pintype "passive"))
      (node (ref "F1") (pin "2") (pinfunction "2_2") (pintype "passive"))
      (node (ref "L17") (pin "2") (pinfunction "2_2") (pintype "passive"))
      (node (ref "R25") (pin "2") (pinfunction "2_2") (pintype "passive"))
    )
    (net (code "78") (name "VBIAS1_VADJ") (class "Default")
      (node (ref "R23") (pin "2") (pinfunction "2_2") (pintype "passive"))
      (node (ref "U5") (pin "6") (pinfunction "VOUTA_6") (pintype "bidirectional"))
    )
    (net (code "79") (name "VBIAS1_VSENSE") (class "Default")
      (node (ref "C65") (pin "1") (pinfunction "C1_1") (pintype "passive"))
      (node (ref "R33") (pin "1") (pinfunction "1_1") (pintype "passive"))
      (node (ref "R34") (pin "2") (pinfunction "2_2") (pintype "passive"))
      (node (ref "U1") (pin "2") (pinfunction "PA1_2") (pintype "bidirectional"))
    )
    (net (code "80") (name "VBIAS2") (class "Default")
      (node (ref "C52") (pin "1") (pinfunction "C1_1") (pintype "passive"))
      (node (ref "C54") (pin "1") (pinfunction "C1_1") (pintype "passive"))
      (node (ref "C56") (pin "1") (pinfunction "C1_1") (pintype "passive"))
      (node (ref "C6") (pin "1") (pinfunction "C1_1") (pintype "passive"))
      (node (ref "F2") (pin "1") (pinfunction "1_1") (pintype "passive"))
      (node (ref "L2") (pin "1") (pinfunction "1_1") (pintype "passive"))
      (node (ref "R30") (pin "2") (pinfunction "2_2") (pintype "passive"))
      (node (ref "R38") (pin "2") (pinfunction "2_2") (pintype "passive"))
    )
    (net (code "81") (name "VBIAS2_EN") (class "Default")
      (node (ref "R18") (pin "2") (pinfunction "2_2") (pintype "passive"))
      (node (ref "U1") (pin "32") (pinfunction "PE13_32") (pintype "bidirectional"))
      (node (ref "U4") (pin "8") (pinfunction "EN/UV_8") (pintype "bidirectional"))
    )
    (net (code "82") (name "VBIAS2_PG") (class "Default")
      (node (ref "R21") (pin "1") (pinfunction "1_1") (pintype "passive"))
      (node (ref "U1") (pin "30") (pinfunction "PE11_30") (pintype "bidirectional"))
      (node (ref "U4") (pin "11") (pinfunction "PG_11") (pintype "bidirectional"))
    )
    (net (code "83") (name "VBIAS2_UNFUSED") (class "Default")
      (node (ref "C39") (pin "1") (pinfunction "C1_1") (pintype "passive"))
      (node (ref "C42") (pin "1") (pinfunction "C1_1") (pintype "passive"))
      (node (ref "C44") (pin "1") (pinfunction "C1_1") (pintype "passive"))
      (node (ref "C46") (pin "1") (pinfunction "C1_1") (pintype "passive"))
      (node (ref "C49") (pin "1") (pinfunction "C1_1") (pintype "passive"))
      (node (ref "F2") (pin "2") (pinfunction "2_2") (pintype "passive"))
      (node (ref "L18") (pin "2") (pinfunction "2_2") (pintype "passive"))
      (node (ref "R27") (pin "2") (pinfunction "2_2") (pintype "passive"))
    )
    (net (code "84") (name "VBIAS2_VADJ") (class "Default")
      (node (ref "R24") (pin "2") (pinfunction "2_2") (pintype "passive"))
      (node (ref "U5") (pin "7") (pinfunction "VOUTB_7") (pintype "bidirectional"))
    )
    (net (code "85") (name "VBIAS2_VSENSE") (class "Default")
      (node (ref "C69") (pin "1") (pinfunction "C1_1") (pintype "passive"))
      (node (ref "R38") (pin "1") (pinfunction "1_1") (pintype "passive"))
      (node (ref "R39") (pin "2") (pinfunction "2_2") (pintype "passive"))
      (node (ref "U1") (pin "3") (pinfunction "PA2_3") (pintype "bidirectional"))
    )
    (net (code "86") (name "VBIAS_VCC") (class "Default")
      (node (ref "C31") (pin "1") (pinfunction "C1_1") (pintype "passive"))
      (node (ref "U4") (pin "13") (pinfunction "SYNC_13") (pintype "bidirectional"))
      (node (ref "U4") (pin "21") (pinfunction "VCC_21") (pintype "bidirectional"))
      (node (ref "U4") (pin "23") (pinfunction "VC_23") (pintype "bidirectional"))
      (node (ref "U4") (pin "28") (pinfunction "VC_28") (pintype "bidirectional"))
    )
    (net (code "87") (name "VIN") (class "Default")
      (node (ref "C37") (pin "1") (pinfunction "C1_1") (pintype "passive"))
      (node (ref "C40") (pin "1") (pinfunction "C1_1") (pintype "passive"))
      (node (ref "C57") (pin "1") (pinfunction "C1_1") (pintype "passive"))
      (node (ref "C61") (pin "1") (pinfunction "C1_1") (pintype "passive"))
      (node (ref "C62") (pin "1") (pinfunction "C1_1") (pintype "passive"))
      (node (ref "C75") (pin "1") (pinfunction "C1_1") (pintype "passive"))
      (node (ref "D5") (pin "C") (pinfunction "C_C") (pintype "passive"))
      (node (ref "F3") (pin "1") (pinfunction "1_1") (pintype "passive"))
      (node (ref "R31") (pin "2") (pinfunction "2_2") (pintype "passive"))
      (node (ref "U4") (pin "3") (pinfunction "VIN_3") (pintype "bidirectional"))
      (node (ref "U4") (pin "4") (pinfunction "VIN_4") (pintype "bidirectional"))
      (node (ref "U4") (pin "5") (pinfunction "VIN_5") (pintype "bidirectional"))
      (node (ref "U4") (pin "6") (pinfunction "VIN_6") (pintype "bidirectional"))
      (node (ref "U7") (pin "11") (pinfunction "VIN_11") (pintype "bidirectional"))
      (node (ref "U7") (pin "14") (pinfunction "EN/UV_14") (pintype "bidirectional"))
      (node (ref "U7") (pin "6") (pinfunction "VIN_6") (pintype "bidirectional"))
    )
    (net (code "88") (name "VIN_VSENSE") (class "Default")
      (node (ref "C59") (pin "1") (pinfunction "C1_1") (pintype "passive"))
      (node (ref "R31") (pin "1") (pinfunction "1_1") (pintype "passive"))
      (node (ref "R32") (pin "2") (pinfunction "2_2") (pintype "passive"))
      (node (ref "U1") (pin "13") (pinfunction "PB14_13") (pintype "bidirectional"))
    )
    (net (code "89") (name "unconnected-(TC1F-S-Pad5)") (class "Default")
      (node (ref "TC1") (pin "5") (pinfunction "S_5") (pintype "passive"))
    )
    (net (code "90") (name "unconnected-(U1-PB7-Pad7)") (class "Default")
      (node (ref "U1") (pin "7") (pinfunction "PB7_7") (pintype "bidirectional"))
    )
    (net (code "91") (name "unconnected-(U1-PB8-Pad8)") (class "Default")
      (node (ref "U1") (pin "8") (pinfunction "PB8_8") (pintype "bidirectional"))
    )
    (net (code "92") (name "unconnected-(U1-PB11-Pad10)") (class "Default")
      (node (ref "U1") (pin "10") (pinfunction "PB11_10") (pintype "bidirectional"))
    )
    (net (code "93") (name "unconnected-(U1-PC0-Pad5)") (class "Default")
      (node (ref "U1") (pin "5") (pinfunction "PC0_5") (pintype "bidirectional"))
    )
    (net (code "94") (name "unconnected-(U1-PC13-Pad22)") (class "Default")
      (node (ref "U1") (pin "22") (pinfunction "PC13_22") (pintype "bidirectional"))
    )
    (net (code "95") (name "unconnected-(U1-PC15-Pad24)") (class "Default")
      (node (ref "U1") (pin "24") (pinfunction "PC15_24") (pintype "bidirectional"))
    )
    (net (code "96") (name "unconnected-(U3-CLK0-Pad13)") (class "Default")
      (node (ref "U3") (pin "13") (pinfunction "CLK0_13") (pintype "bidirectional"))
    )
    (net (code "97") (name "unconnected-(U3-CLK2-Pad9)") (class "Default")
      (node (ref "U3") (pin "9") (pinfunction "CLK2_9") (pintype "bidirectional"))
    )
    (net (code "98") (name "unconnected-(U3-CLK3-Pad8)") (class "Default")
      (node (ref "U3") (pin "8") (pinfunction "CLK3_8") (pintype "bidirectional"))
    )
    (net (code "99") (name "unconnected-(U3-CLK4-Pad19)") (class "Default")
      (node (ref "U3") (pin "19") (pinfunction "CLK4_19") (pintype "bidirectional"))
    )
    (net (code "100") (name "unconnected-(U3-CLK6-Pad16)") (class "Default")
      (node (ref "U3") (pin "16") (pinfunction "CLK6_16") (pintype "bidirectional"))
    )
    (net (code "101") (name "unconnected-(U3-INTR-Pad3)") (class "Default")
      (node (ref "U3") (pin "3") (pinfunction "INTR_3") (pintype "bidirectional"))
    )
    (net (code "102") (name "unconnected-(U3-XB-Pad2)") (class "Default")
      (node (ref "U3") (pin "2") (pinfunction "XB_2") (pintype "bidirectional"))
    )
    (net (code "103") (name "unconnected-(U4C-CLKOUT-Pad14)") (class "Default")
      (node (ref "U4") (pin "14") (pinfunction "CLKOUT_14") (pintype "bidirectional"))
    )
    (net (code "104") (name "unconnected-(U5-VOUTC-Pad8)") (class "Default")
      (node (ref "U5") (pin "8") (pinfunction "VOUTC_8") (pintype "bidirectional"))
    )
    (net (code "105") (name "unconnected-(U5-VOUTD-Pad9)") (class "Default")
      (node (ref "U5") (pin "9") (pinfunction "VOUTD_9") (pintype "bidirectional"))
    )
    (net (code "106") (name "unconnected-(U5-~{BSY}-Pad5)") (class "Default")
      (node (ref "U5") (pin "5") (pinfunction "~{BSY}_5") (pintype "bidirectional"))
    )
    (net (code "107") (name "unconnected-(U6-PG-Pad5)") (class "Default")
      (node (ref "U6") (pin "5") (pinfunction "PG_5") (pintype "bidirectional"))
    )
    (net (code "108") (name "unconnected-(U7-CLKOUT-Pad16)") (class "Default")
      (node (ref "U7") (pin "16") (pinfunction "CLKOUT_16") (pintype "bidirectional"))
    )
    (net (code "109") (name "unconnected-(U7-PG-Pad1)") (class "Default")
      (node (ref "U7") (pin "1") (pinfunction "PG_1") (pintype "bidirectional"))
    )
    (net (code "110") (name "~{REF_SYNTH_OE}") (class "Default")
      (node (ref "R11") (pin "1") (pinfunction "1_1") (pintype "passive"))
      (node (ref "U1") (pin "23") (pinfunction "PC14_23") (pintype "bidirectional"))
      (node (ref "U3") (pin "7") (pinfunction "~{OE}_7") (pintype "bidirectional"))
    )
    (net (code "111") (name "~{RESET}") (class "Default")
      (node (ref "R1") (pin "1") (pinfunction "1_1") (pintype "passive"))
      (node (ref "TC1") (pin "10") (pinfunction "S_10") (pintype "passive"))
      (node (ref "U1") (pin "9") (pinfunction "~{RESET}_9") (pintype "bidirectional"))
    )
  )
)
